# mcat-4cu-b-v2.net
KiCad netlist of a schematic drawn in EAGLE
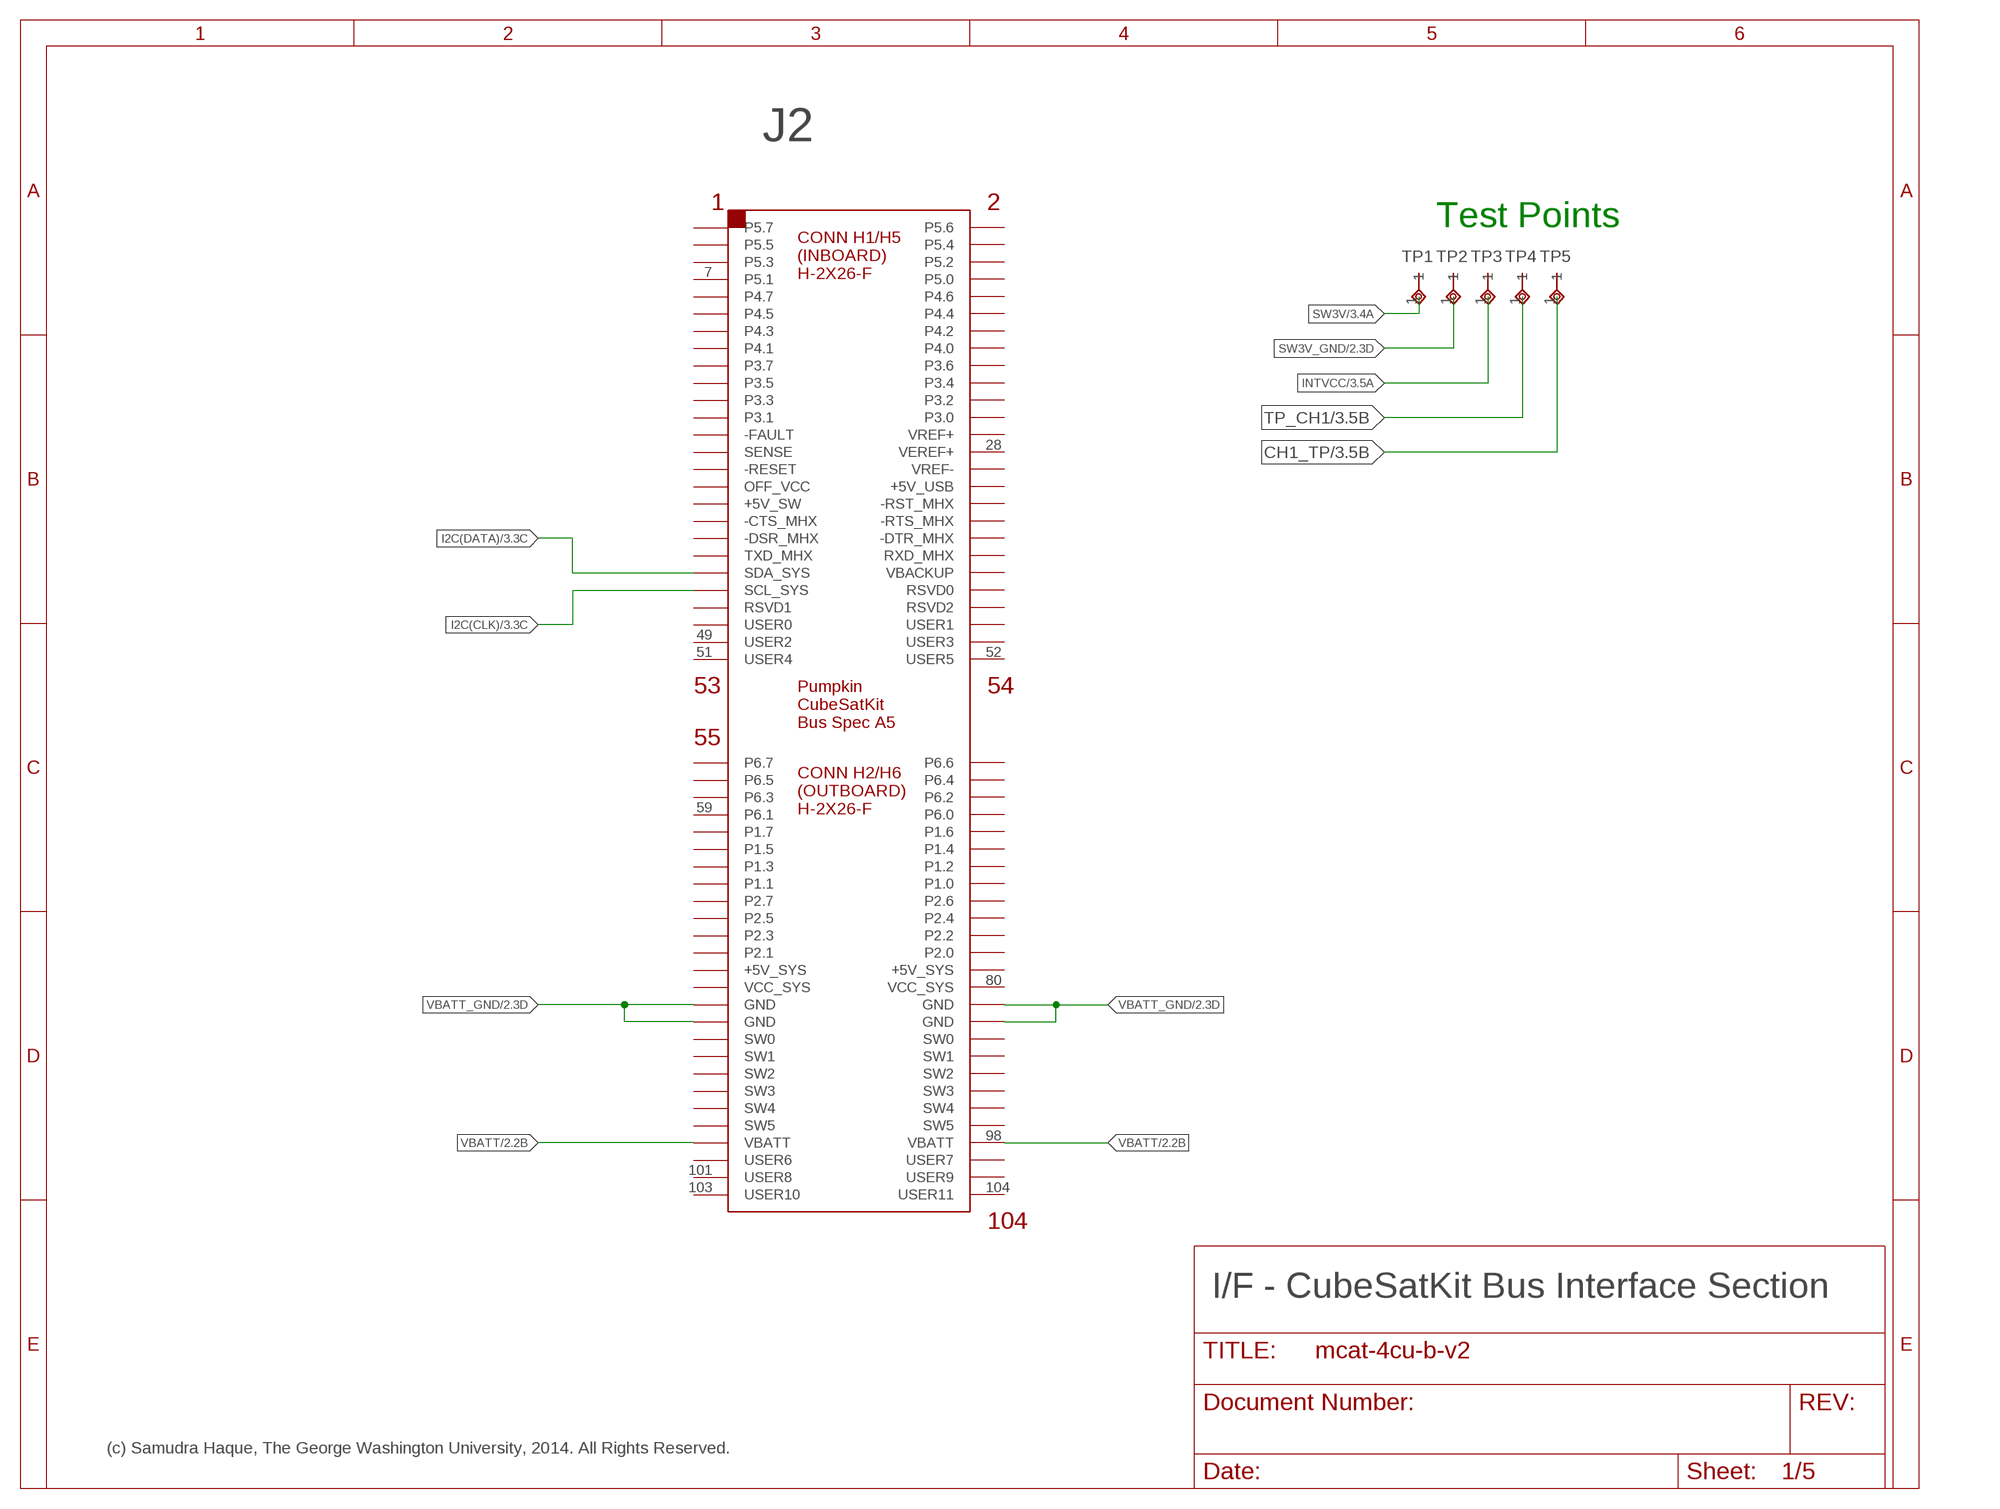
[diagram p0: schematic, sheet 1]
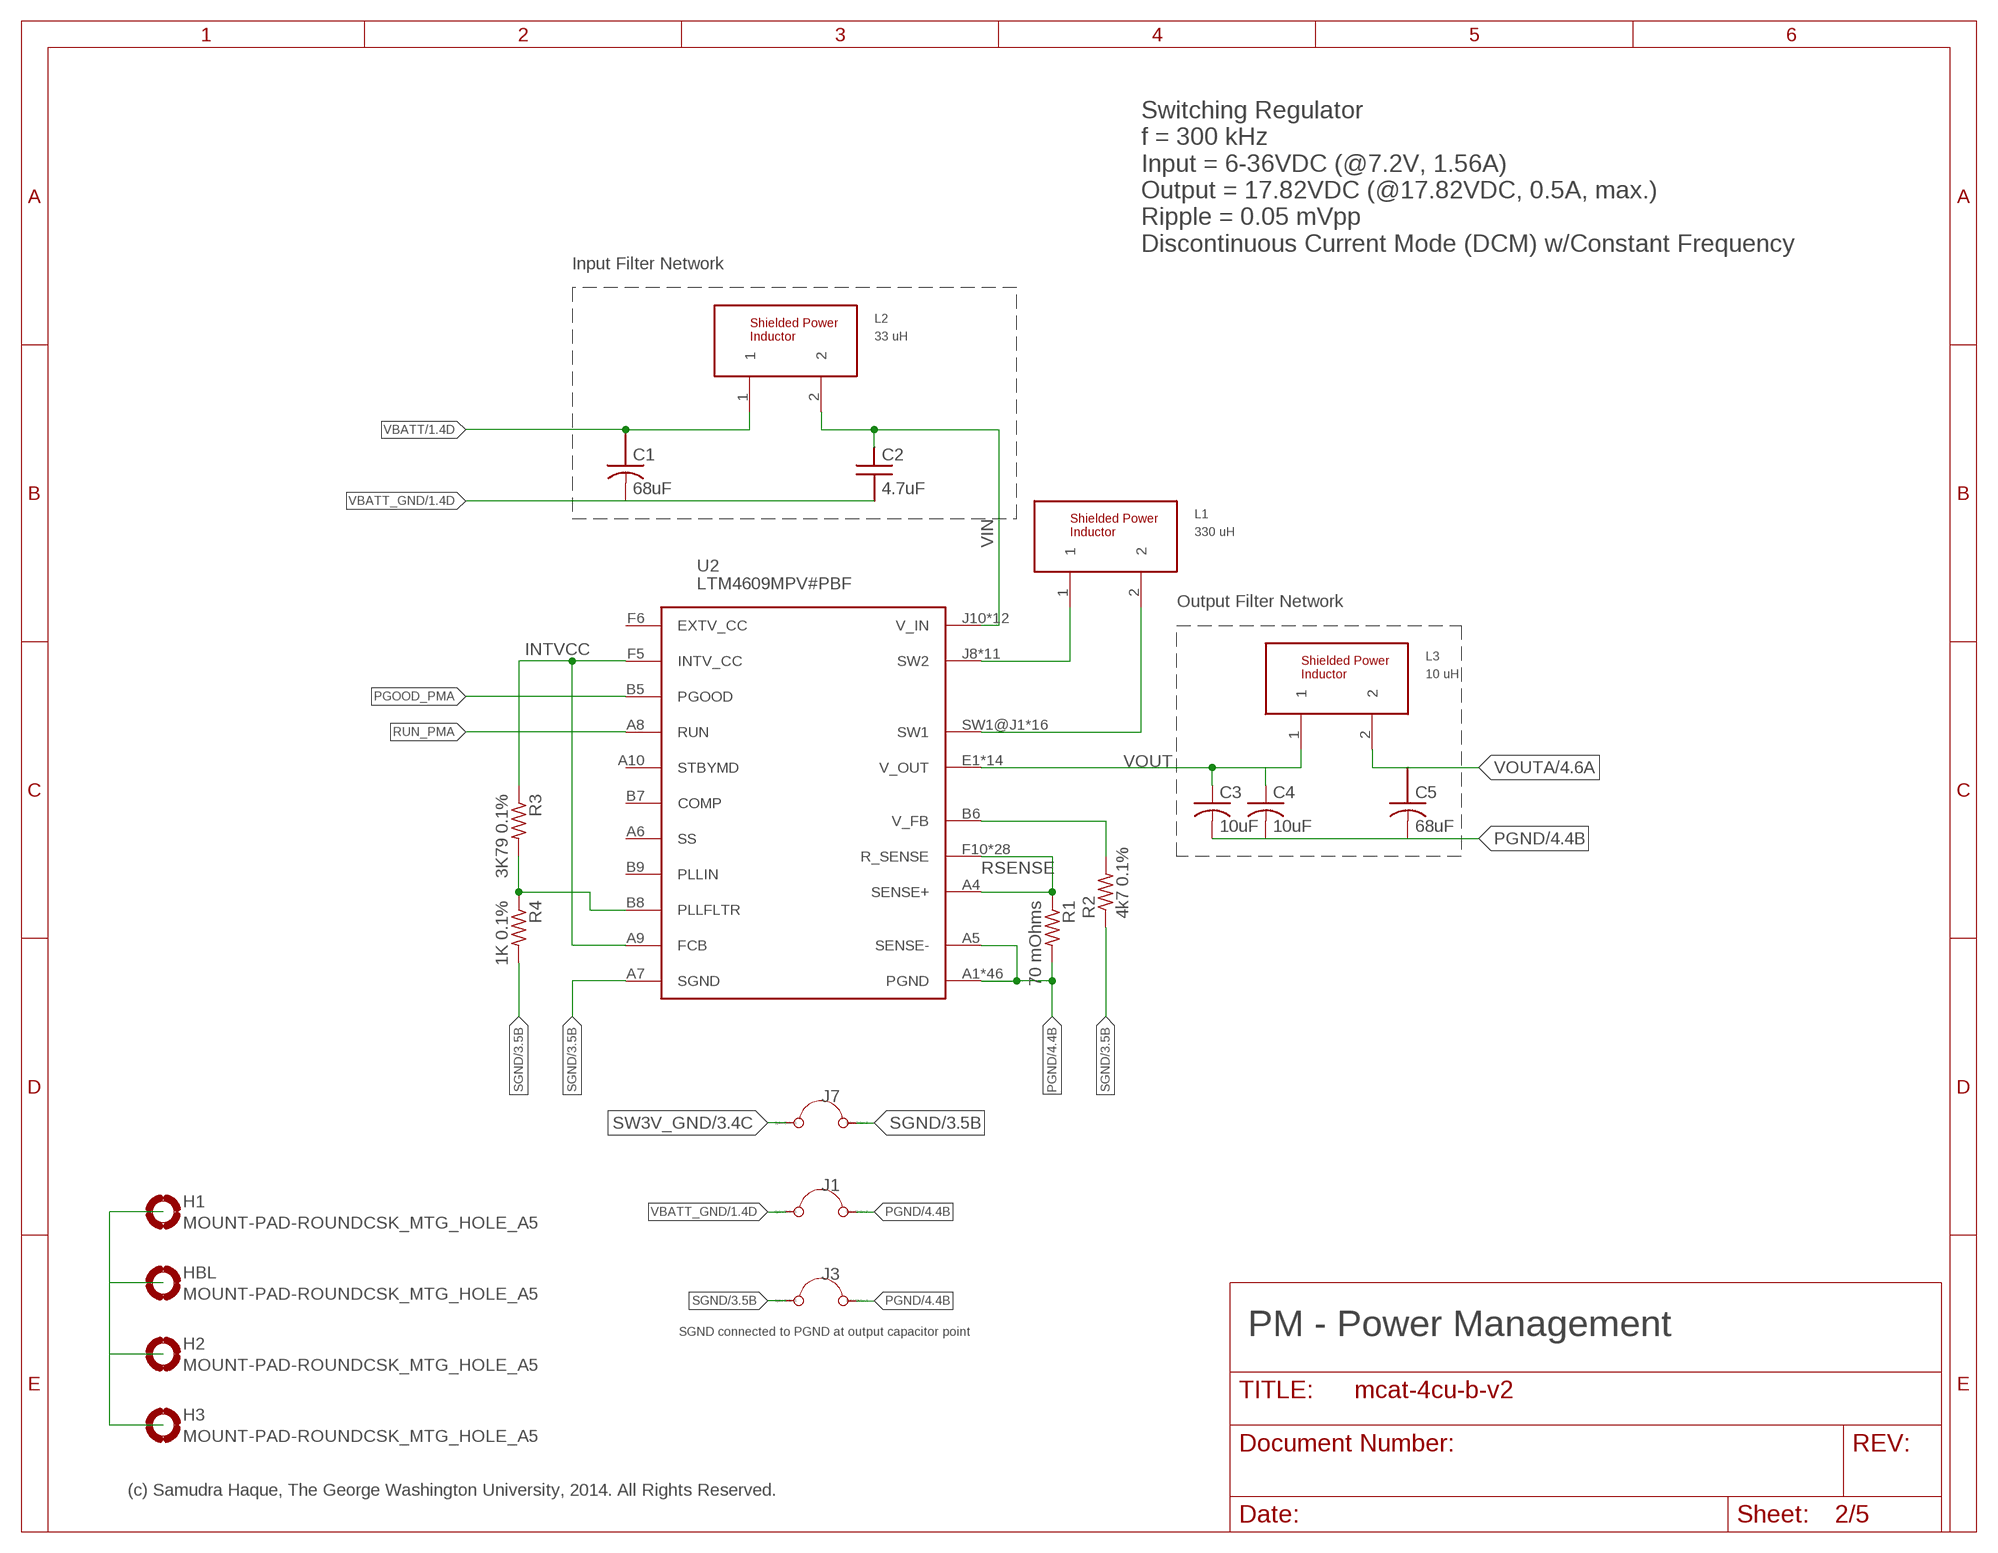
[diagram p1: schematic, sheet 2]
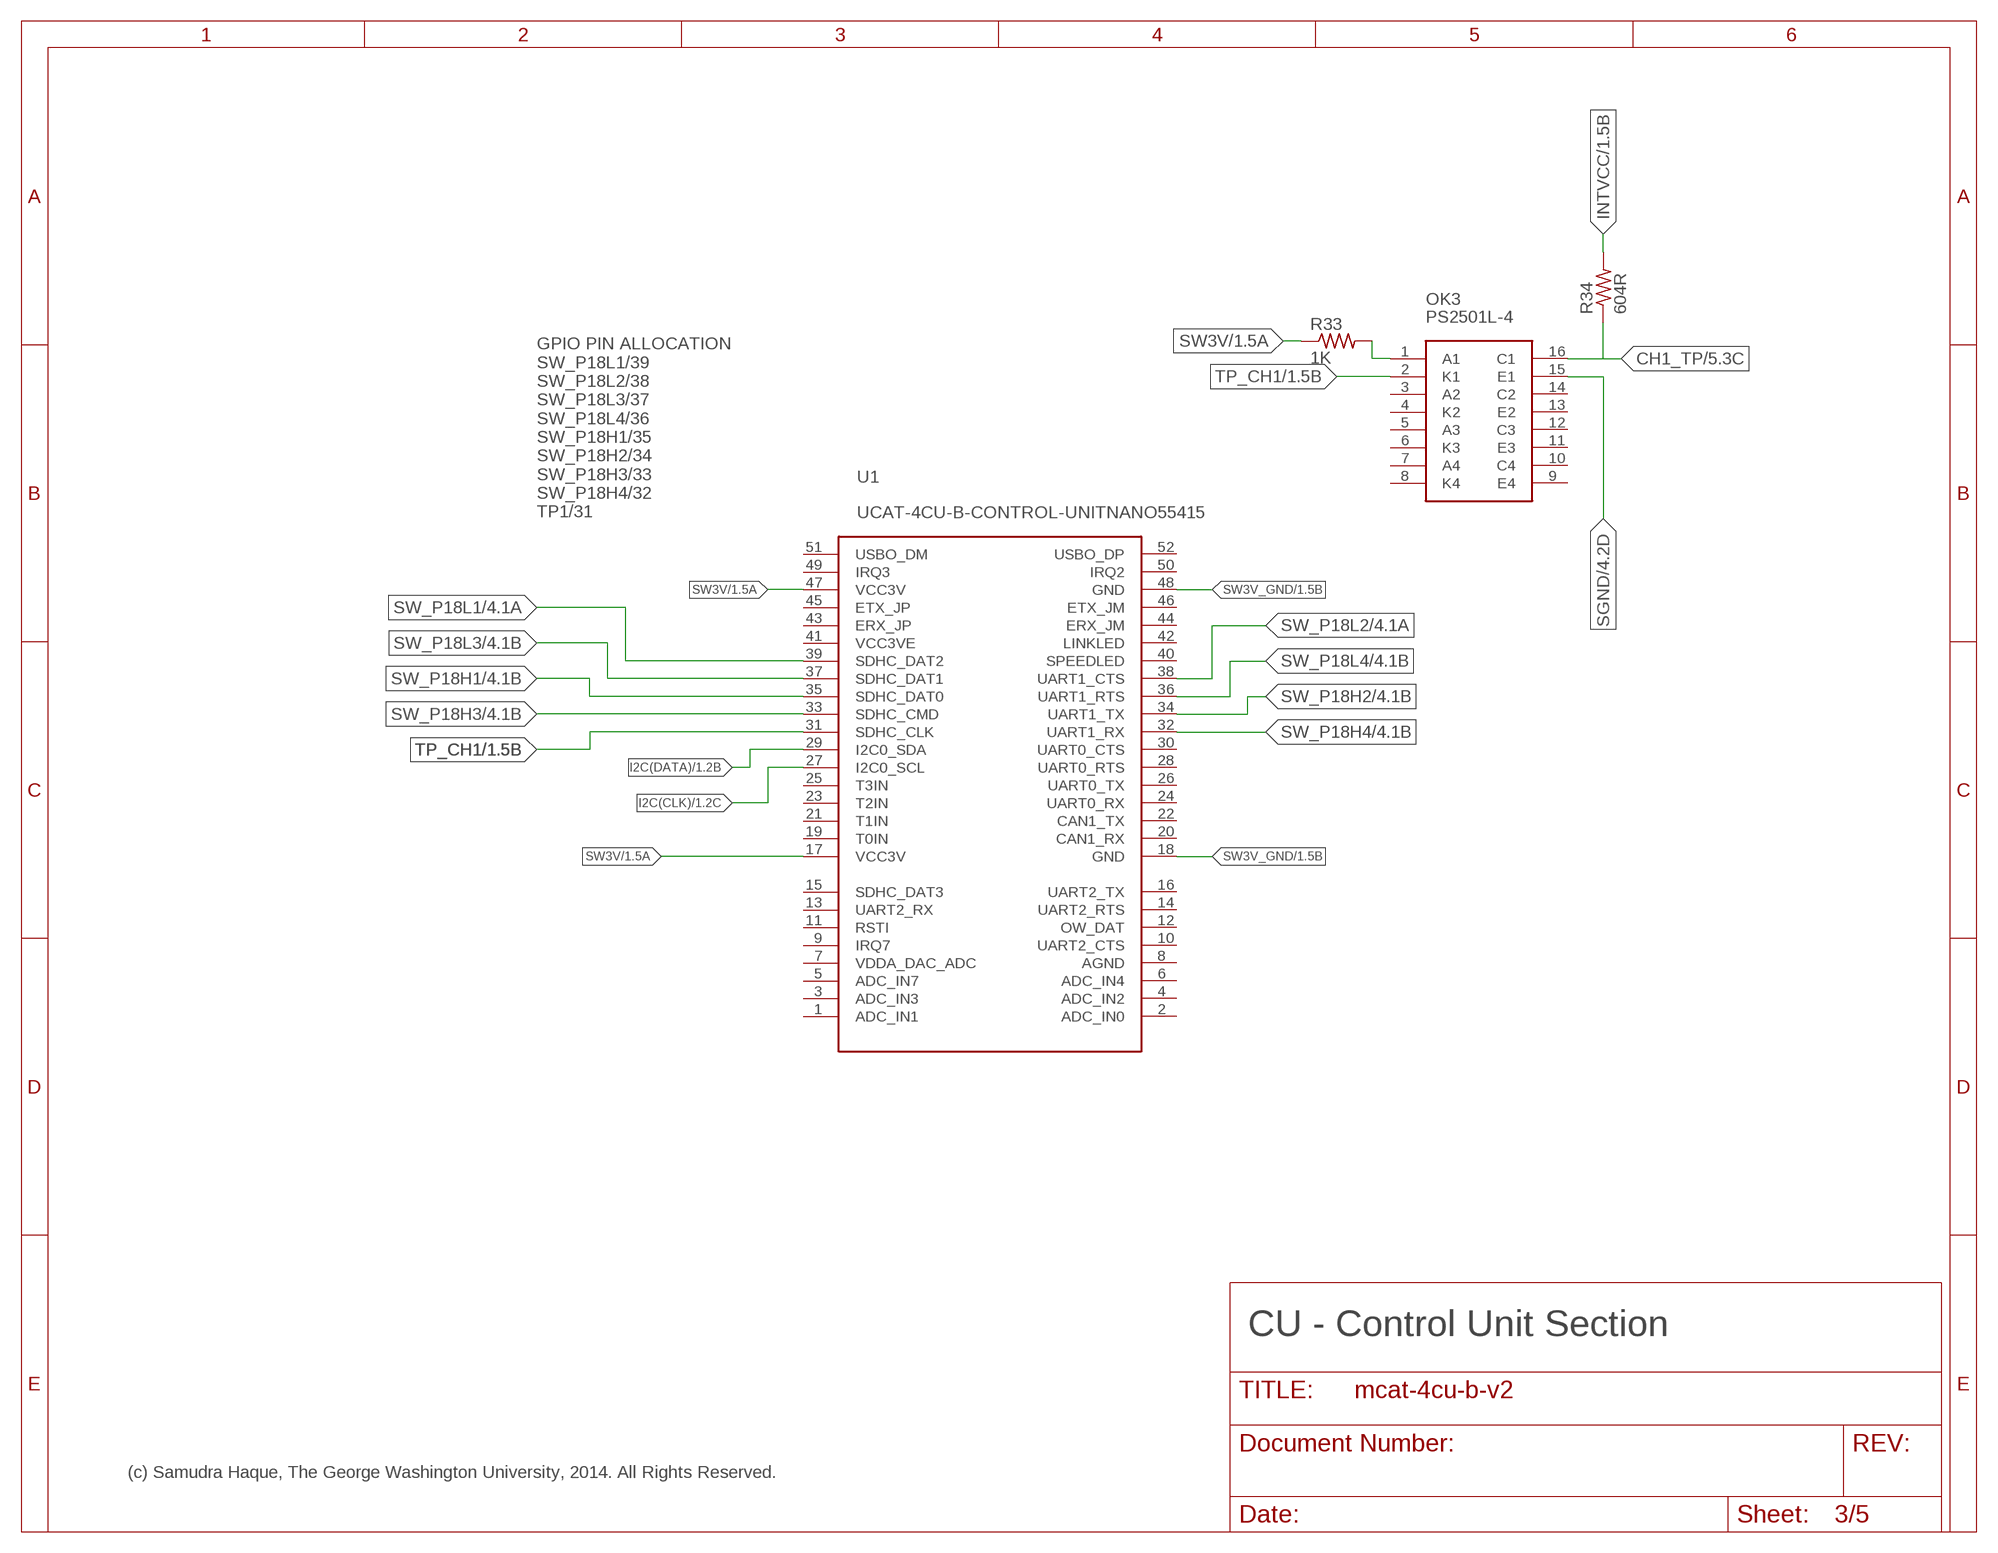
[diagram p2: schematic, sheet 3]
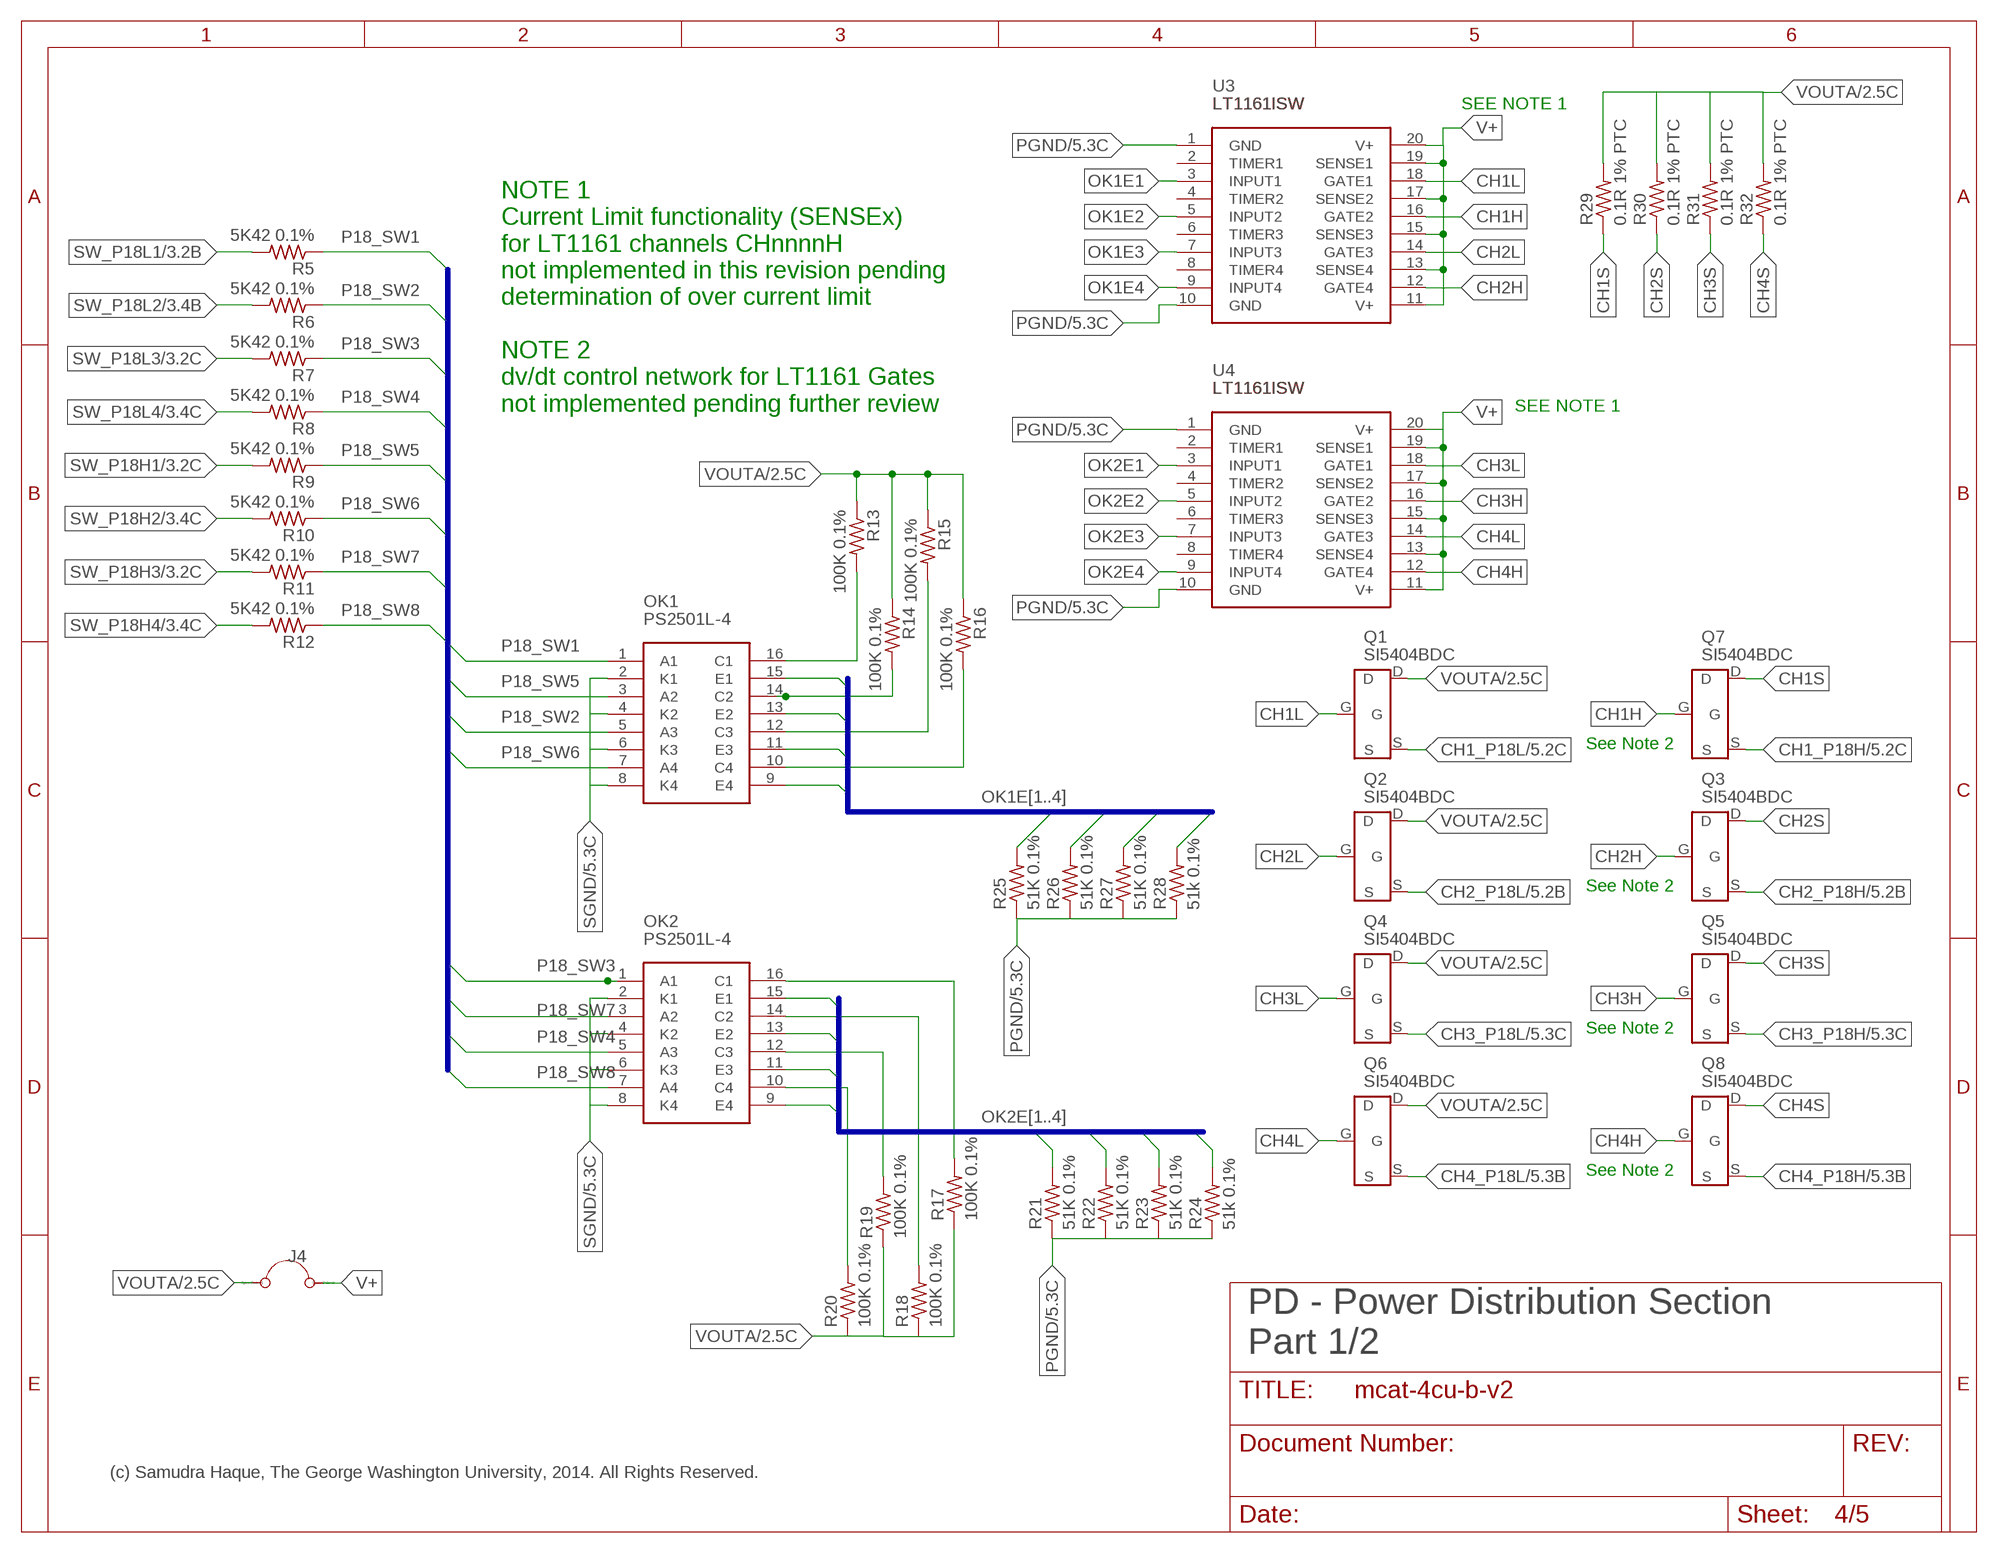
[diagram p3: schematic, sheet 4]
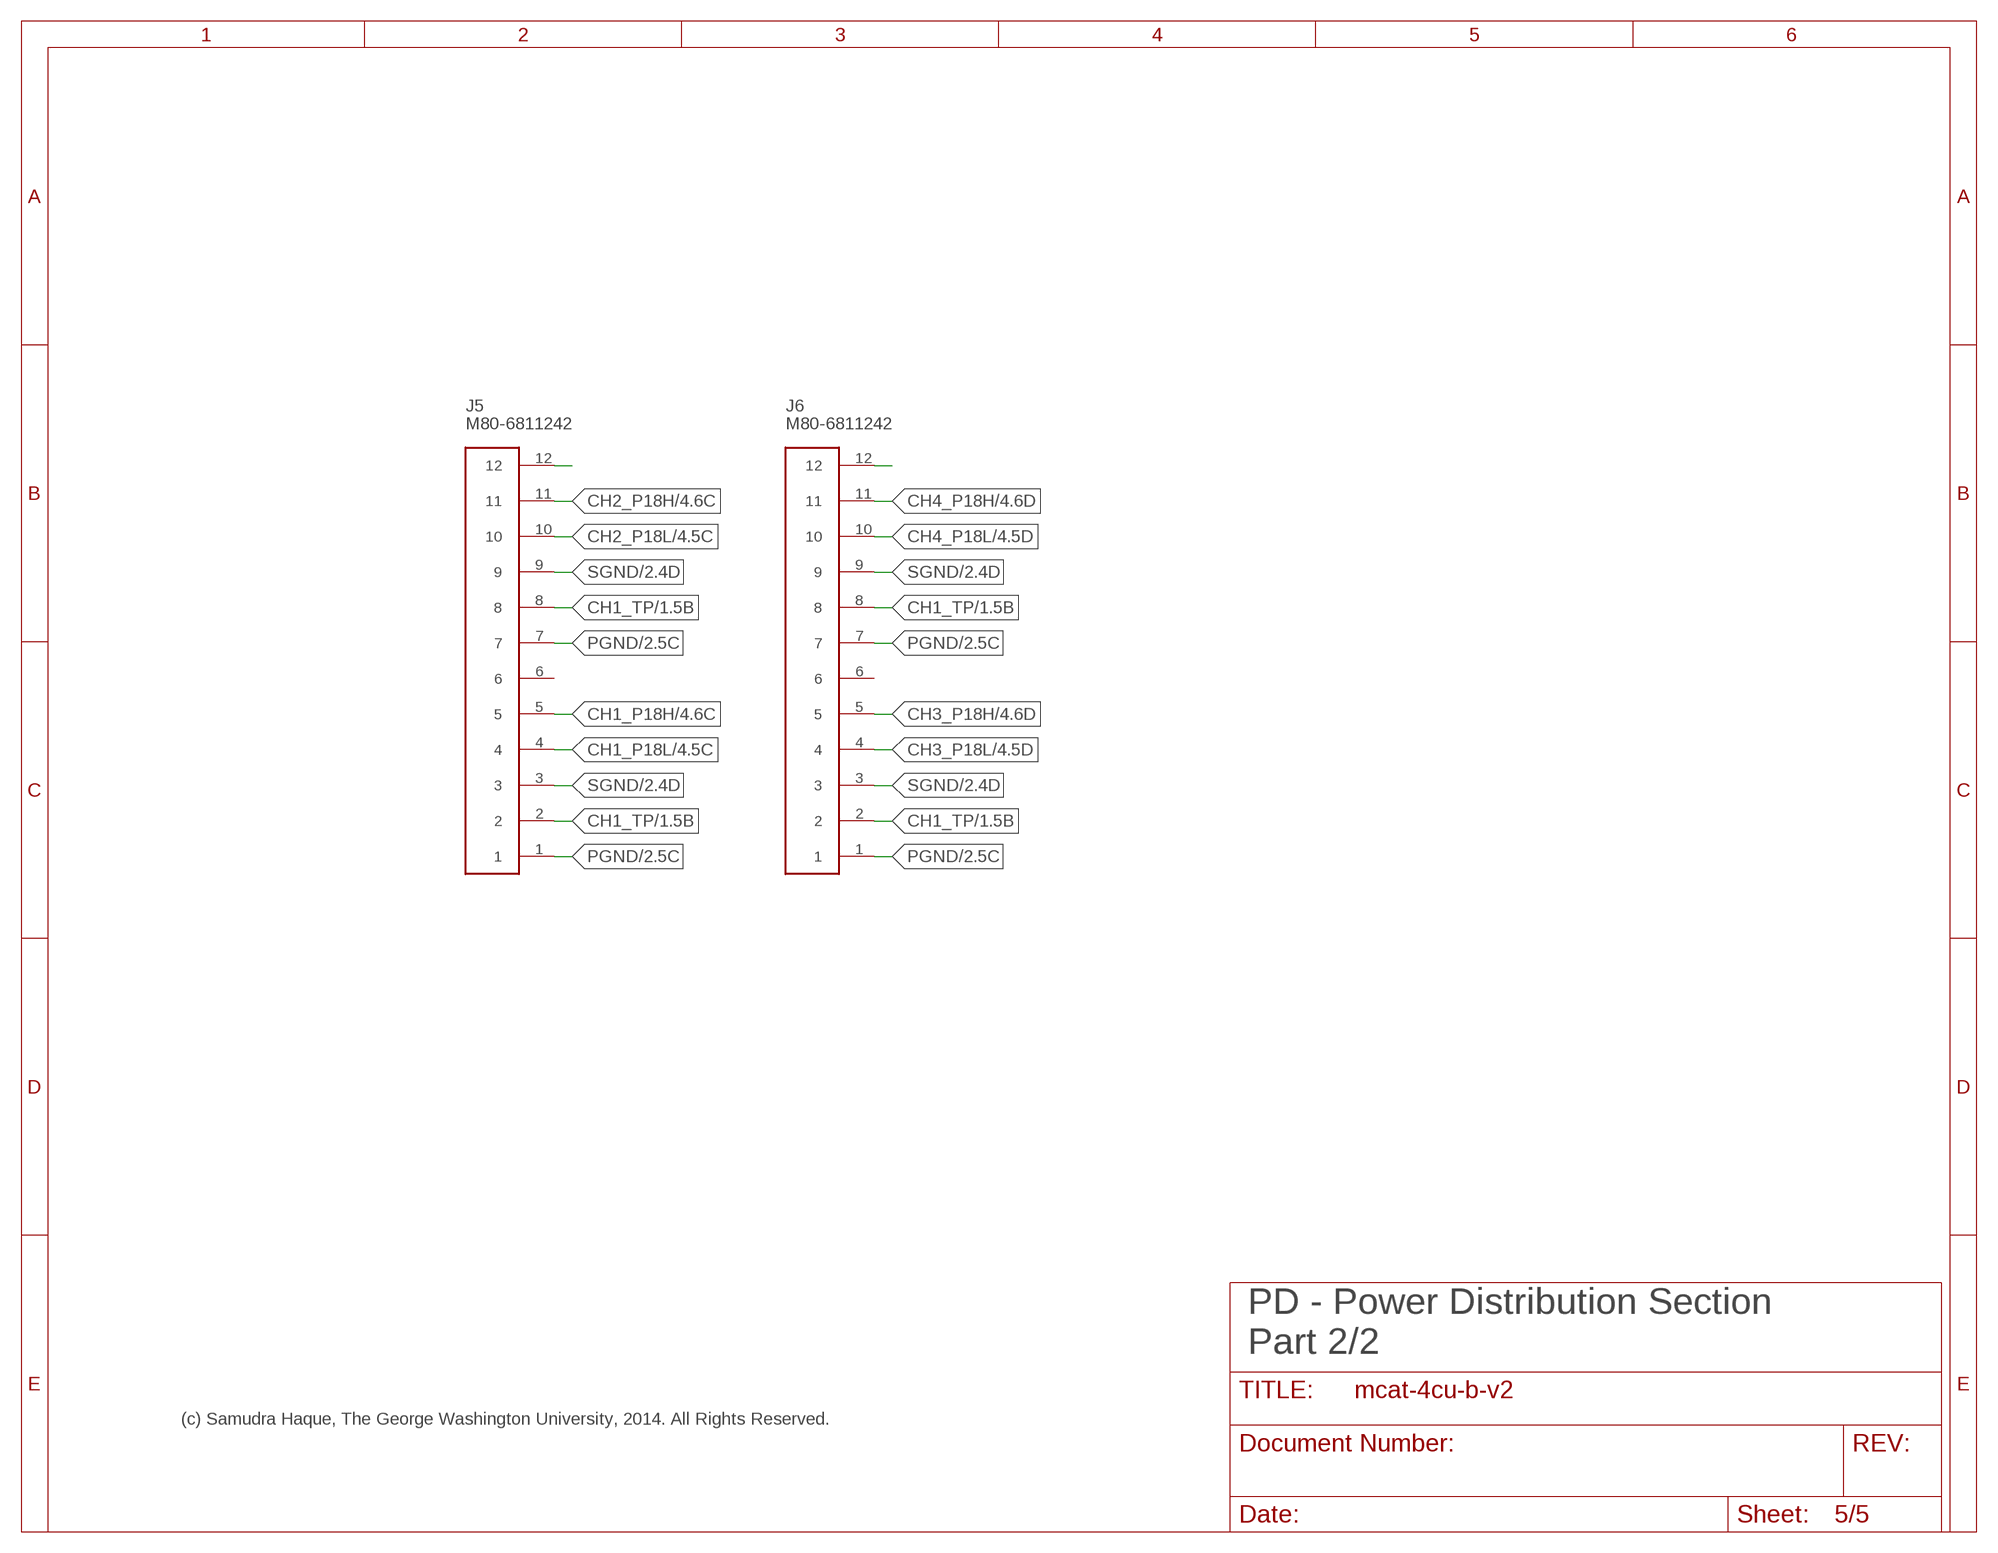
[diagram p4: schematic, sheet 5]

(export (version "E")
  (design (tool "Eeschema 10.0.6"))
  (components
    (comp (ref "J4")
      (value "JUMPER")
      (footprint "eagle-import:05")
      (libsource (lib "eagle-import") (part "JUMPER"))
    )
    (comp (ref "OK1")
      (value "PS2501L-4")
      (footprint "eagle-import:PS2501L-4")
      (libsource (lib "eagle-import") (part "PS2501L-4"))
    )
    (comp (ref "OK2")
      (value "PS2501L-4")
      (footprint "eagle-import:PS2501L-4")
      (libsource (lib "eagle-import") (part "PS2501L-4"))
    )
    (comp (ref "Q1")
      (value "SI5404BDC")
      (footprint "eagle-import:1206-8-CHIPFET")
      (libsource (lib "eagle-import") (part "SI5404BDC"))
    )
    (comp (ref "Q2")
      (value "SI5404BDC")
      (footprint "eagle-import:1206-8-CHIPFET")
      (libsource (lib "eagle-import") (part "SI5404BDC"))
    )
    (comp (ref "Q3")
      (value "SI5404BDC")
      (footprint "eagle-import:1206-8-CHIPFET")
      (libsource (lib "eagle-import") (part "SI5404BDC"))
    )
    (comp (ref "Q4")
      (value "SI5404BDC")
      (footprint "eagle-import:1206-8-CHIPFET")
      (libsource (lib "eagle-import") (part "SI5404BDC"))
    )
    (comp (ref "Q5")
      (value "SI5404BDC")
      (footprint "eagle-import:1206-8-CHIPFET")
      (libsource (lib "eagle-import") (part "SI5404BDC"))
    )
    (comp (ref "Q6")
      (value "SI5404BDC")
      (footprint "eagle-import:1206-8-CHIPFET")
      (libsource (lib "eagle-import") (part "SI5404BDC"))
    )
    (comp (ref "Q7")
      (value "SI5404BDC")
      (footprint "eagle-import:1206-8-CHIPFET")
      (libsource (lib "eagle-import") (part "SI5404BDC"))
    )
    (comp (ref "Q8")
      (value "SI5404BDC")
      (footprint "eagle-import:1206-8-CHIPFET")
      (libsource (lib "eagle-import") (part "SI5404BDC"))
    )
    (comp (ref "R5")
      (value "5K42 0.1%")
      (footprint "eagle-import:R1206")
      (libsource (lib "eagle-import") (part "resistor_R-US_R1206"))
    )
    (comp (ref "R6")
      (value "5K42 0.1%")
      (footprint "eagle-import:R1206")
      (libsource (lib "eagle-import") (part "resistor_R-US_R1206"))
    )
    (comp (ref "R7")
      (value "5K42 0.1%")
      (footprint "eagle-import:R1206")
      (libsource (lib "eagle-import") (part "resistor_R-US_R1206"))
    )
    (comp (ref "R8")
      (value "5K42 0.1%")
      (footprint "eagle-import:R1206")
      (libsource (lib "eagle-import") (part "resistor_R-US_R1206"))
    )
    (comp (ref "R9")
      (value "5K42 0.1%")
      (footprint "eagle-import:R1206")
      (libsource (lib "eagle-import") (part "resistor_R-US_R1206"))
    )
    (comp (ref "R10")
      (value "5K42 0.1%")
      (footprint "eagle-import:R1206")
      (libsource (lib "eagle-import") (part "resistor_R-US_R1206"))
    )
    (comp (ref "R11")
      (value "5K42 0.1%")
      (footprint "eagle-import:R1206")
      (libsource (lib "eagle-import") (part "resistor_R-US_R1206"))
    )
    (comp (ref "R12")
      (value "5K42 0.1%")
      (footprint "eagle-import:R1206")
      (libsource (lib "eagle-import") (part "resistor_R-US_R1206"))
    )
    (comp (ref "R13")
      (value "100K 0.1%")
      (footprint "eagle-import:R0402")
      (libsource (lib "eagle-import") (part "resistor_R-US_R0402"))
    )
    (comp (ref "R14")
      (value "100K 0.1%")
      (footprint "eagle-import:R0402")
      (libsource (lib "eagle-import") (part "resistor_R-US_R0402"))
    )
    (comp (ref "R15")
      (value "100K 0.1%")
      (footprint "eagle-import:R0402")
      (libsource (lib "eagle-import") (part "resistor_R-US_R0402"))
    )
    (comp (ref "R16")
      (value "100K 0.1%")
      (footprint "eagle-import:R0402")
      (libsource (lib "eagle-import") (part "resistor_R-US_R0402"))
    )
    (comp (ref "R17")
      (value "100K 0.1%")
      (footprint "eagle-import:R0402")
      (libsource (lib "eagle-import") (part "resistor_R-US_R0402"))
    )
    (comp (ref "R18")
      (value "100K 0.1%")
      (footprint "eagle-import:R0402")
      (libsource (lib "eagle-import") (part "resistor_R-US_R0402"))
    )
    (comp (ref "R19")
      (value "100K 0.1%")
      (footprint "eagle-import:R0402")
      (libsource (lib "eagle-import") (part "resistor_R-US_R0402"))
    )
    (comp (ref "R20")
      (value "100K 0.1%")
      (footprint "eagle-import:R0402")
      (libsource (lib "eagle-import") (part "resistor_R-US_R0402"))
    )
    (comp (ref "R21")
      (value "51K 0.1%")
      (footprint "eagle-import:R0603")
      (libsource (lib "eagle-import") (part "resistor_R-US_R0603"))
    )
    (comp (ref "R22")
      (value "51K 0.1%")
      (footprint "eagle-import:R0603")
      (libsource (lib "eagle-import") (part "resistor_R-US_R0603"))
    )
    (comp (ref "R23")
      (value "51K 0.1%")
      (footprint "eagle-import:R0603")
      (libsource (lib "eagle-import") (part "resistor_R-US_R0603"))
    )
    (comp (ref "R24")
      (value "51k 0.1%")
      (footprint "eagle-import:R0603")
      (libsource (lib "eagle-import") (part "resistor_R-US_R0603"))
    )
    (comp (ref "R25")
      (value "51K 0.1%")
      (footprint "eagle-import:R0603")
      (libsource (lib "eagle-import") (part "resistor_R-US_R0603"))
    )
    (comp (ref "R26")
      (value "51K 0.1%")
      (footprint "eagle-import:R0603")
      (libsource (lib "eagle-import") (part "resistor_R-US_R0603"))
    )
    (comp (ref "R27")
      (value "51K 0.1%")
      (footprint "eagle-import:R0603")
      (libsource (lib "eagle-import") (part "resistor_R-US_R0603"))
    )
    (comp (ref "R28")
      (value "51k 0.1%")
      (footprint "eagle-import:R0603")
      (libsource (lib "eagle-import") (part "resistor_R-US_R0603"))
    )
    (comp (ref "R29")
      (value "0.1R 1% PTC")
      (footprint "eagle-import:R0402")
      (libsource (lib "eagle-import") (part "R-US_R0402"))
    )
    (comp (ref "R30")
      (value "0.1R 1% PTC")
      (footprint "eagle-import:R0402")
      (libsource (lib "eagle-import") (part "R-US_R0402"))
    )
    (comp (ref "R31")
      (value "0.1R 1% PTC")
      (footprint "eagle-import:R0402")
      (libsource (lib "eagle-import") (part "R-US_R0402"))
    )
    (comp (ref "R32")
      (value "0.1R 1% PTC")
      (footprint "eagle-import:R0402")
      (libsource (lib "eagle-import") (part "R-US_R0402"))
    )
    (comp (ref "U3")
      (value "LT1161ISW")
      (footprint "eagle-import:20-LEAD-PLASTIC-SO")
      (libsource (lib "eagle-import") (part "LT1161ISW"))
    )
    (comp (ref "U4")
      (value "LT1161ISW")
      (footprint "eagle-import:20-LEAD-PLASTIC-SO")
      (libsource (lib "eagle-import") (part "LT1161ISW"))
    )
    (comp (ref "J5")
      (value "M80-6811242")
      (footprint "eagle-import:M80-68112")
      (libsource (lib "eagle-import") (part "M80-6811242"))
    )
    (comp (ref "J6")
      (value "M80-6811242")
      (footprint "eagle-import:M80-68112")
      (libsource (lib "eagle-import") (part "M80-6811242"))
    )
    (comp (ref "OK3")
      (value "PS2501L-4")
      (footprint "eagle-import:PS2501L-4")
      (libsource (lib "eagle-import") (part "PS2501L-4"))
    )
    (comp (ref "R33")
      (value "1K")
      (footprint "eagle-import:R0805")
      (libsource (lib "eagle-import") (part "resistor_R-US_R0805"))
    )
    (comp (ref "R34")
      (value "604R")
      (footprint "eagle-import:R0805")
      (libsource (lib "eagle-import") (part "resistor_R-US_R0805"))
    )
    (comp (ref "U1")
      (value "UCAT-4CU-B-CONTROL-UNITNANO55415")
      (footprint "eagle-import:MOLEX-MINI-PCI-EXPRESS-8MM-52CKT")
      (libsource (lib "eagle-import") (part "UCAT-4CU-B-CONTROL-UNITNANO55415"))
    )
    (comp (ref "J2")
      (value "CSK-BUS-CONN2X2X26")
      (footprint "eagle-import:CSK-BUS-PKG")
      (libsource (lib "eagle-import") (part "CSK-BUS-CONN2X2X26"))
    )
    (comp (ref "TP1")
      (value "1P-1508-0-57-15-00-00-03-0")
      (footprint "eagle-import:1P-TP-MILLMAX-11")
      (libsource (lib "eagle-import") (part "1P-1508-0-57-15-00-00-03-0"))
    )
    (comp (ref "TP2")
      (value "1P-1508-0-57-15-00-00-03-0")
      (footprint "eagle-import:1P-TP-MILLMAX-11")
      (libsource (lib "eagle-import") (part "1P-1508-0-57-15-00-00-03-0"))
    )
    (comp (ref "TP3")
      (value "1P-1508-0-57-15-00-00-03-0")
      (footprint "eagle-import:1P-TP-MILLMAX-11")
      (libsource (lib "eagle-import") (part "1P-1508-0-57-15-00-00-03-0"))
    )
    (comp (ref "TP4")
      (value "1P-1508-0-57-15-00-00-03-0")
      (footprint "eagle-import:1P-TP-MILLMAX-11")
      (libsource (lib "eagle-import") (part "1P-1508-0-57-15-00-00-03-0"))
    )
    (comp (ref "TP5")
      (value "1P-1508-0-57-15-00-00-03-0")
      (footprint "eagle-import:1P-TP-MILLMAX-11")
      (libsource (lib "eagle-import") (part "1P-1508-0-57-15-00-00-03-0"))
    )
    (comp (ref "C1")
      (value "68uF")
      (footprint "eagle-import:OS-CON-SVPF-F12")
      (libsource (lib "eagle-import") (part "OSCON-50SVPF68M"))
    )
    (comp (ref "C2")
      (value "4.7uF")
      (footprint "eagle-import:MLCC-X7R-1210")
      (libsource (lib "eagle-import") (part "AVX-LD105C475KAB2A"))
    )
    (comp (ref "C3")
      (value "10uF")
      (footprint "eagle-import:C1210K")
      (libsource (lib "eagle-import") (part "C-USC1210K"))
    )
    (comp (ref "C4")
      (value "10uF")
      (footprint "eagle-import:C1210K")
      (libsource (lib "eagle-import") (part "C-USC1210K"))
    )
    (comp (ref "C5")
      (value "68uF")
      (footprint "eagle-import:OS-CON-SVPF-F12")
      (libsource (lib "eagle-import") (part "OSCON-50SVPF68M"))
    )
    (comp (ref "H1")
      (value "MOUNT-PAD-ROUNDCSK_MTG_HOLE_A5")
      (footprint "eagle-import:CSK_MOUNTING_HOLE")
      (libsource (lib "eagle-import") (part "MOUNT-PAD-ROUNDCSK_MTG_HOLE_A5"))
    )
    (comp (ref "H2")
      (value "MOUNT-PAD-ROUNDCSK_MTG_HOLE_A5")
      (footprint "eagle-import:CSK_MOUNTING_HOLE")
      (libsource (lib "eagle-import") (part "MOUNT-PAD-ROUNDCSK_MTG_HOLE_A5"))
    )
    (comp (ref "H3")
      (value "MOUNT-PAD-ROUNDCSK_MTG_HOLE_A5")
      (footprint "eagle-import:CSK_MOUNTING_HOLE")
      (libsource (lib "eagle-import") (part "MOUNT-PAD-ROUNDCSK_MTG_HOLE_A5"))
    )
    (comp (ref "HBL")
      (value "MOUNT-PAD-ROUNDCSK_MTG_HOLE_A5")
      (footprint "eagle-import:CSK_MOUNTING_HOLE")
      (libsource (lib "eagle-import") (part "MOUNT-PAD-ROUNDCSK_MTG_HOLE_A5"))
    )
    (comp (ref "J1")
      (value "JUMPER")
      (footprint "eagle-import:05")
      (libsource (lib "eagle-import") (part "JUMPER"))
    )
    (comp (ref "J3")
      (value "JUMPER")
      (footprint "eagle-import:05")
      (libsource (lib "eagle-import") (part "JUMPER"))
    )
    (comp (ref "J7")
      (value "JUMPER")
      (footprint "eagle-import:05")
      (libsource (lib "eagle-import") (part "JUMPER"))
    )
    (comp (ref "L1")
      (value "330 uH")
      (footprint "eagle-import:MSS1048")
      (libsource (lib "eagle-import") (part "MSS1048-334KL_"))
    )
    (comp (ref "L2")
      (value "33 uH")
      (footprint "eagle-import:MSS1048")
      (libsource (lib "eagle-import") (part "MSS1038-333ML_"))
    )
    (comp (ref "L3")
      (value "10 uH")
      (footprint "eagle-import:SERIES-POWER-INDUCTORS")
      (fields (field (name "MF") "PANASONIC") (field (name "MPN") "ELL5PS100M"))
      (libsource (lib "eagle-import") (part "ELL-5PS100M"))
    )
    (comp (ref "R1")
      (value "70 mOhms")
      (footprint "eagle-import:R1206")
      (libsource (lib "eagle-import") (part "resistor_R-US_R1206"))
    )
    (comp (ref "R2")
      (value "4k7 0.1%")
      (footprint "eagle-import:R0603")
      (libsource (lib "eagle-import") (part "resistor_R-US_R0603"))
    )
    (comp (ref "R3")
      (value "3K79 0.1%")
      (footprint "eagle-import:R0805")
      (libsource (lib "eagle-import") (part "R-US_R0805"))
    )
    (comp (ref "R4")
      (value "1K 0.1%")
      (footprint "eagle-import:R0805")
      (libsource (lib "eagle-import") (part "R-US_R0805"))
    )
    (comp (ref "U2")
      (value "LTM4609MPV#PBF")
      (footprint "eagle-import:LGA-141-LTC-05-08-1840-B")
      (libsource (lib "eagle-import") (part "LTM4609MPV#PBFROHS/HITEMP"))
    )
  )
  (nets
    (net (code "3") (name "CH1H") (class "Default")
      (node (ref "Q7") (pin "G") (pinfunction "G_G") (pintype "bidirectional"))
      (node (ref "U3") (pin "16") (pinfunction "GATE2_16") (pintype "bidirectional"))
    )
    (net (code "4") (name "CH1L") (class "Default")
      (node (ref "Q1") (pin "G") (pinfunction "G_G") (pintype "bidirectional"))
      (node (ref "U3") (pin "18") (pinfunction "GATE1_18") (pintype "bidirectional"))
    )
    (net (code "5") (name "CH1S") (class "Default")
      (node (ref "Q7") (pin "D") (pinfunction "D_D") (pintype "bidirectional"))
      (node (ref "R29") (pin "1") (pinfunction "1_1") (pintype "passive"))
    )
    (net (code "6") (name "CH1_P18H") (class "Default")
      (node (ref "J5") (pin "5") (pinfunction "5_5") (pintype "bidirectional"))
      (node (ref "Q7") (pin "S") (pinfunction "S_S") (pintype "bidirectional"))
    )
    (net (code "7") (name "CH1_P18L") (class "Default")
      (node (ref "J5") (pin "4") (pinfunction "4_4") (pintype "bidirectional"))
      (node (ref "Q1") (pin "S") (pinfunction "S_S") (pintype "bidirectional"))
    )
    (net (code "8") (name "CH1_TP") (class "Default")
      (node (ref "J5") (pin "2") (pinfunction "2_2") (pintype "bidirectional"))
      (node (ref "J5") (pin "8") (pinfunction "8_8") (pintype "bidirectional"))
      (node (ref "J6") (pin "2") (pinfunction "2_2") (pintype "bidirectional"))
      (node (ref "J6") (pin "8") (pinfunction "8_8") (pintype "bidirectional"))
      (node (ref "OK3") (pin "16") (pinfunction "C1_16") (pintype "bidirectional"))
      (node (ref "R34") (pin "1") (pinfunction "1_1") (pintype "passive"))
      (node (ref "TP5") (pin "1") (pinfunction "1_1") (pintype "bidirectional"))
    )
    (net (code "9") (name "CH2H") (class "Default")
      (node (ref "Q3") (pin "G") (pinfunction "G_G") (pintype "bidirectional"))
      (node (ref "U3") (pin "12") (pinfunction "GATE4_12") (pintype "bidirectional"))
    )
    (net (code "10") (name "CH2L") (class "Default")
      (node (ref "Q2") (pin "G") (pinfunction "G_G") (pintype "bidirectional"))
      (node (ref "U3") (pin "14") (pinfunction "GATE3_14") (pintype "bidirectional"))
    )
    (net (code "11") (name "CH2S") (class "Default")
      (node (ref "Q3") (pin "D") (pinfunction "D_D") (pintype "bidirectional"))
      (node (ref "R30") (pin "1") (pinfunction "1_1") (pintype "passive"))
    )
    (net (code "12") (name "CH2_P18H") (class "Default")
      (node (ref "J5") (pin "11") (pinfunction "11_11") (pintype "bidirectional"))
      (node (ref "Q3") (pin "S") (pinfunction "S_S") (pintype "bidirectional"))
    )
    (net (code "13") (name "CH2_P18L") (class "Default")
      (node (ref "J5") (pin "10") (pinfunction "10_10") (pintype "bidirectional"))
      (node (ref "Q2") (pin "S") (pinfunction "S_S") (pintype "bidirectional"))
    )
    (net (code "14") (name "CH3H") (class "Default")
      (node (ref "Q5") (pin "G") (pinfunction "G_G") (pintype "bidirectional"))
      (node (ref "U4") (pin "16") (pinfunction "GATE2_16") (pintype "bidirectional"))
    )
    (net (code "15") (name "CH3L") (class "Default")
      (node (ref "Q4") (pin "G") (pinfunction "G_G") (pintype "bidirectional"))
      (node (ref "U4") (pin "18") (pinfunction "GATE1_18") (pintype "bidirectional"))
    )
    (net (code "16") (name "CH3S") (class "Default")
      (node (ref "Q5") (pin "D") (pinfunction "D_D") (pintype "bidirectional"))
      (node (ref "R31") (pin "1") (pinfunction "1_1") (pintype "passive"))
    )
    (net (code "17") (name "CH3_P18H") (class "Default")
      (node (ref "J6") (pin "5") (pinfunction "5_5") (pintype "bidirectional"))
      (node (ref "Q5") (pin "S") (pinfunction "S_S") (pintype "bidirectional"))
    )
    (net (code "18") (name "CH3_P18L") (class "Default")
      (node (ref "J6") (pin "4") (pinfunction "4_4") (pintype "bidirectional"))
      (node (ref "Q4") (pin "S") (pinfunction "S_S") (pintype "bidirectional"))
    )
    (net (code "19") (name "CH4H") (class "Default")
      (node (ref "Q8") (pin "G") (pinfunction "G_G") (pintype "bidirectional"))
      (node (ref "U4") (pin "12") (pinfunction "GATE4_12") (pintype "bidirectional"))
    )
    (net (code "20") (name "CH4L") (class "Default")
      (node (ref "Q6") (pin "G") (pinfunction "G_G") (pintype "bidirectional"))
      (node (ref "U4") (pin "14") (pinfunction "GATE3_14") (pintype "bidirectional"))
    )
    (net (code "21") (name "CH4S") (class "Default")
      (node (ref "Q8") (pin "D") (pinfunction "D_D") (pintype "bidirectional"))
      (node (ref "R32") (pin "1") (pinfunction "1_1") (pintype "passive"))
    )
    (net (code "22") (name "CH4_P18H") (class "Default")
      (node (ref "J6") (pin "11") (pinfunction "11_11") (pintype "bidirectional"))
      (node (ref "Q8") (pin "S") (pinfunction "S_S") (pintype "bidirectional"))
    )
    (net (code "23") (name "CH4_P18L") (class "Default")
      (node (ref "J6") (pin "10") (pinfunction "10_10") (pintype "bidirectional"))
      (node (ref "Q6") (pin "S") (pinfunction "S_S") (pintype "bidirectional"))
    )
    (net (code "24") (name "I2C(CLK)") (class "Default")
      (node (ref "J2") (pin "43") (pinfunction "SCL_SYS_43") (pintype "bidirectional"))
      (node (ref "U1") (pin "27") (pinfunction "I2C0_SCL_27") (pintype "bidirectional"))
    )
    (net (code "25") (name "I2C(DATA)") (class "Default")
      (node (ref "J2") (pin "41") (pinfunction "SDA_SYS_41") (pintype "bidirectional"))
      (node (ref "U1") (pin "29") (pinfunction "I2C0_SDA_29") (pintype "bidirectional"))
    )
    (net (code "26") (name "INTVCC") (class "Default")
      (node (ref "R3") (pin "1") (pinfunction "1_1") (pintype "passive"))
      (node (ref "R34") (pin "2") (pinfunction "2_2") (pintype "passive"))
      (node (ref "TP3") (pin "1") (pinfunction "1_1") (pintype "bidirectional"))
      (node (ref "U2") (pin "A9") (pinfunction "FCB_A9") (pintype "bidirectional"))
      (node (ref "U2") (pin "F5") (pinfunction "INTV_CC_F5") (pintype "bidirectional"))
    )
    (net (code "27") (name "Net-(H1-MOUNT)") (class "Default")
      (node (ref "H1") (pin "P$1") (pinfunction "MOUNT_P$1") (pintype "passive"))
      (node (ref "H2") (pin "P$1") (pinfunction "MOUNT_P$1") (pintype "passive"))
      (node (ref "H3") (pin "P$1") (pinfunction "MOUNT_P$1") (pintype "passive"))
      (node (ref "HBL") (pin "P$1") (pinfunction "MOUNT_P$1") (pintype "passive"))
    )
    (net (code "28") (name "Net-(L1-Pad1)") (class "Default")
      (node (ref "L1") (pin "1") (pinfunction "1_1") (pintype "bidirectional"))
      (node (ref "U2") (pin "J8") (pinfunction "SW2_J8") (pintype "bidirectional"))
      (node (ref "U2") (pin "J9") (pinfunction "SW2_J9") (pintype "bidirectional"))
      (node (ref "U2") (pin "K7") (pinfunction "SW2_K7") (pintype "bidirectional"))
      (node (ref "U2") (pin "K8") (pinfunction "SW2_K8") (pintype "bidirectional"))
      (node (ref "U2") (pin "K9") (pinfunction "SW2_K9") (pintype "bidirectional"))
      (node (ref "U2") (pin "L7") (pinfunction "SW2_L7") (pintype "bidirectional"))
      (node (ref "U2") (pin "L8") (pinfunction "SW2_L8") (pintype "bidirectional"))
      (node (ref "U2") (pin "L9") (pinfunction "SW2_L9") (pintype "bidirectional"))
      (node (ref "U2") (pin "M7") (pinfunction "SW2_M7") (pintype "bidirectional"))
      (node (ref "U2") (pin "M8") (pinfunction "SW2_M8") (pintype "bidirectional"))
      (node (ref "U2") (pin "M9") (pinfunction "SW2_M9") (pintype "bidirectional"))
    )
    (net (code "29") (name "Net-(L1-Pad2)") (class "Default")
      (node (ref "L1") (pin "2") (pinfunction "2_2") (pintype "bidirectional"))
      (node (ref "U2") (pin "SW1@J1") (pinfunction "SW1_SW1@J1") (pintype "bidirectional"))
      (node (ref "U2") (pin "SW1@J2") (pinfunction "SW1_SW1@J2") (pintype "bidirectional"))
      (node (ref "U2") (pin "SW1@J3") (pinfunction "SW1_SW1@J3") (pintype "bidirectional"))
      (node (ref "U2") (pin "SW1@J4") (pinfunction "SW1_SW1@J4") (pintype "bidirectional"))
      (node (ref "U2") (pin "SW1@K1") (pinfunction "SW1_SW1@K1") (pintype "bidirectional"))
      (node (ref "U2") (pin "SW1@K2") (pinfunction "SW1_SW1@K2") (pintype "bidirectional"))
      (node (ref "U2") (pin "SW1@K3") (pinfunction "SW1_SW1@K3") (pintype "bidirectional"))
      (node (ref "U2") (pin "SW1@K4") (pinfunction "SW1_SW1@K4") (pintype "bidirectional"))
      (node (ref "U2") (pin "SW1@L1") (pinfunction "SW1_SW1@L1") (pintype "bidirectional"))
      (node (ref "U2") (pin "SW1@L2") (pinfunction "SW1_SW1@L2") (pintype "bidirectional"))
      (node (ref "U2") (pin "SW1@L3") (pinfunction "SW1_SW1@L3") (pintype "bidirectional"))
      (node (ref "U2") (pin "SW1@L4") (pinfunction "SW1_SW1@L4") (pintype "bidirectional"))
      (node (ref "U2") (pin "SW1@M1") (pinfunction "SW1_SW1@M1") (pintype "bidirectional"))
      (node (ref "U2") (pin "SW1@M2") (pinfunction "SW1_SW1@M2") (pintype "bidirectional"))
      (node (ref "U2") (pin "SW1@M3") (pinfunction "SW1_SW1@M3") (pintype "bidirectional"))
      (node (ref "U2") (pin "SW1@M4") (pinfunction "SW1_SW1@M4") (pintype "bidirectional"))
    )
    (net (code "30") (name "Net-(OK1-C1)") (class "Default")
      (node (ref "OK1") (pin "16") (pinfunction "C1_16") (pintype "bidirectional"))
      (node (ref "R13") (pin "2") (pinfunction "2_2") (pintype "passive"))
    )
    (net (code "31") (name "Net-(OK1-C2)") (class "Default")
      (node (ref "OK1") (pin "14") (pinfunction "C2_14") (pintype "bidirectional"))
      (node (ref "R14") (pin "2") (pinfunction "2_2") (pintype "passive"))
    )
    (net (code "32") (name "Net-(OK1-C3)") (class "Default")
      (node (ref "OK1") (pin "12") (pinfunction "C3_12") (pintype "bidirectional"))
      (node (ref "R15") (pin "2") (pinfunction "2_2") (pintype "passive"))
    )
    (net (code "33") (name "Net-(OK1-C4)") (class "Default")
      (node (ref "OK1") (pin "10") (pinfunction "C4_10") (pintype "bidirectional"))
      (node (ref "R16") (pin "2") (pinfunction "2_2") (pintype "passive"))
    )
    (net (code "34") (name "Net-(OK2-C1)") (class "Default")
      (node (ref "OK2") (pin "16") (pinfunction "C1_16") (pintype "bidirectional"))
      (node (ref "R17") (pin "2") (pinfunction "2_2") (pintype "passive"))
    )
    (net (code "35") (name "Net-(OK2-C2)") (class "Default")
      (node (ref "OK2") (pin "14") (pinfunction "C2_14") (pintype "bidirectional"))
      (node (ref "R18") (pin "2") (pinfunction "2_2") (pintype "passive"))
    )
    (net (code "36") (name "Net-(OK2-C3)") (class "Default")
      (node (ref "OK2") (pin "12") (pinfunction "C3_12") (pintype "bidirectional"))
      (node (ref "R19") (pin "2") (pinfunction "2_2") (pintype "passive"))
    )
    (net (code "37") (name "Net-(OK2-C4)") (class "Default")
      (node (ref "OK2") (pin "10") (pinfunction "C4_10") (pintype "bidirectional"))
      (node (ref "R20") (pin "2") (pinfunction "2_2") (pintype "passive"))
    )
    (net (code "38") (name "Net-(OK3-A1)") (class "Default")
      (node (ref "OK3") (pin "1") (pinfunction "A1_1") (pintype "bidirectional"))
      (node (ref "R33") (pin "2") (pinfunction "2_2") (pintype "passive"))
    )
    (net (code "39") (name "Net-(U2-PLLFLTR)") (class "Default")
      (node (ref "R3") (pin "2") (pinfunction "2_2") (pintype "passive"))
      (node (ref "R4") (pin "1") (pinfunction "1_1") (pintype "passive"))
      (node (ref "U2") (pin "B8") (pinfunction "PLLFLTR_B8") (pintype "bidirectional"))
    )
    (net (code "40") (name "Net-(U2-V_FB)") (class "Default")
      (node (ref "R2") (pin "2") (pinfunction "2_2") (pintype "passive"))
      (node (ref "U2") (pin "B6") (pinfunction "V_FB_B6") (pintype "bidirectional"))
    )
    (net (code "41") (name "OK1E1") (class "Default")
      (node (ref "OK1") (pin "15") (pinfunction "E1_15") (pintype "bidirectional"))
      (node (ref "R25") (pin "2") (pinfunction "2_2") (pintype "passive"))
      (node (ref "U3") (pin "3") (pinfunction "INPUT1_3") (pintype "bidirectional"))
    )
    (net (code "42") (name "OK1E2") (class "Default")
      (node (ref "OK1") (pin "13") (pinfunction "E2_13") (pintype "bidirectional"))
      (node (ref "R26") (pin "2") (pinfunction "2_2") (pintype "passive"))
      (node (ref "U3") (pin "5") (pinfunction "INPUT2_5") (pintype "bidirectional"))
    )
    (net (code "43") (name "OK1E3") (class "Default")
      (node (ref "OK1") (pin "11") (pinfunction "E3_11") (pintype "bidirectional"))
      (node (ref "R27") (pin "2") (pinfunction "2_2") (pintype "passive"))
      (node (ref "U3") (pin "7") (pinfunction "INPUT3_7") (pintype "bidirectional"))
    )
    (net (code "44") (name "OK1E4") (class "Default")
      (node (ref "OK1") (pin "9") (pinfunction "E4_9") (pintype "bidirectional"))
      (node (ref "R28") (pin "2") (pinfunction "2_2") (pintype "passive"))
      (node (ref "U3") (pin "9") (pinfunction "INPUT4_9") (pintype "bidirectional"))
    )
    (net (code "45") (name "OK2E1") (class "Default")
      (node (ref "OK2") (pin "15") (pinfunction "E1_15") (pintype "bidirectional"))
      (node (ref "R21") (pin "2") (pinfunction "2_2") (pintype "passive"))
      (node (ref "U4") (pin "3") (pinfunction "INPUT1_3") (pintype "bidirectional"))
    )
    (net (code "46") (name "OK2E2") (class "Default")
      (node (ref "OK2") (pin "13") (pinfunction "E2_13") (pintype "bidirectional"))
      (node (ref "R22") (pin "2") (pinfunction "2_2") (pintype "passive"))
      (node (ref "U4") (pin "5") (pinfunction "INPUT2_5") (pintype "bidirectional"))
    )
    (net (code "47") (name "OK2E3") (class "Default")
      (node (ref "OK2") (pin "11") (pinfunction "E3_11") (pintype "bidirectional"))
      (node (ref "R23") (pin "2") (pinfunction "2_2") (pintype "passive"))
      (node (ref "U4") (pin "7") (pinfunction "INPUT3_7") (pintype "bidirectional"))
    )
    (net (code "48") (name "OK2E4") (class "Default")
      (node (ref "OK2") (pin "9") (pinfunction "E4_9") (pintype "bidirectional"))
      (node (ref "R24") (pin "2") (pinfunction "2_2") (pintype "passive"))
      (node (ref "U4") (pin "9") (pinfunction "INPUT4_9") (pintype "bidirectional"))
    )
    (net (code "49") (name "P18_SW1") (class "Default")
      (node (ref "OK1") (pin "1") (pinfunction "A1_1") (pintype "bidirectional"))
      (node (ref "R5") (pin "1") (pinfunction "1_1") (pintype "passive"))
    )
    (net (code "50") (name "P18_SW2") (class "Default")
      (node (ref "OK1") (pin "5") (pinfunction "A3_5") (pintype "bidirectional"))
      (node (ref "R6") (pin "1") (pinfunction "1_1") (pintype "passive"))
    )
    (net (code "51") (name "P18_SW3") (class "Default")
      (node (ref "OK2") (pin "1") (pinfunction "A1_1") (pintype "bidirectional"))
      (node (ref "R7") (pin "1") (pinfunction "1_1") (pintype "passive"))
    )
    (net (code "52") (name "P18_SW4") (class "Default")
      (node (ref "OK2") (pin "5") (pinfunction "A3_5") (pintype "bidirectional"))
      (node (ref "R8") (pin "1") (pinfunction "1_1") (pintype "passive"))
    )
    (net (code "53") (name "P18_SW5") (class "Default")
      (node (ref "OK1") (pin "3") (pinfunction "A2_3") (pintype "bidirectional"))
      (node (ref "R9") (pin "1") (pinfunction "1_1") (pintype "passive"))
    )
    (net (code "54") (name "P18_SW6") (class "Default")
      (node (ref "OK1") (pin "7") (pinfunction "A4_7") (pintype "bidirectional"))
      (node (ref "R10") (pin "1") (pinfunction "1_1") (pintype "passive"))
    )
    (net (code "55") (name "P18_SW7") (class "Default")
      (node (ref "OK2") (pin "3") (pinfunction "A2_3") (pintype "bidirectional"))
      (node (ref "R11") (pin "1") (pinfunction "1_1") (pintype "passive"))
    )
    (net (code "56") (name "P18_SW8") (class "Default")
      (node (ref "OK2") (pin "7") (pinfunction "A4_7") (pintype "bidirectional"))
      (node (ref "R12") (pin "1") (pinfunction "1_1") (pintype "passive"))
    )
    (net (code "57") (name "PGND") (class "Default")
      (node (ref "C3") (pin "2") (pinfunction "2_2") (pintype "passive"))
      (node (ref "C4") (pin "2") (pinfunction "2_2") (pintype "passive"))
      (node (ref "C5") (pin "K1") (pinfunction "K_K1") (pintype "passive"))
      (node (ref "J1") (pin "2") (pinfunction "-_2") (pintype "passive"))
      (node (ref "J3") (pin "2") (pinfunction "-_2") (pintype "passive"))
      (node (ref "J5") (pin "1") (pinfunction "1_1") (pintype "bidirectional"))
      (node (ref "J5") (pin "7") (pinfunction "7_7") (pintype "bidirectional"))
      (node (ref "J6") (pin "1") (pinfunction "1_1") (pintype "bidirectional"))
      (node (ref "J6") (pin "7") (pinfunction "7_7") (pintype "bidirectional"))
      (node (ref "R1") (pin "2") (pinfunction "2_2") (pintype "passive"))
      (node (ref "R21") (pin "1") (pinfunction "1_1") (pintype "passive"))
      (node (ref "R22") (pin "1") (pinfunction "1_1") (pintype "passive"))
      (node (ref "R23") (pin "1") (pinfunction "1_1") (pintype "passive"))
      (node (ref "R24") (pin "1") (pinfunction "1_1") (pintype "passive"))
      (node (ref "R25") (pin "1") (pinfunction "1_1") (pintype "passive"))
      (node (ref "R26") (pin "1") (pinfunction "1_1") (pintype "passive"))
      (node (ref "R27") (pin "1") (pinfunction "1_1") (pintype "passive"))
      (node (ref "R28") (pin "1") (pinfunction "1_1") (pintype "passive"))
      (node (ref "U2") (pin "A1") (pinfunction "PGND_A1") (pintype "bidirectional"))
      (node (ref "U2") (pin "A11") (pinfunction "PGND_A11") (pintype "bidirectional"))
      (node (ref "U2") (pin "A12") (pinfunction "PGND_A12") (pintype "bidirectional"))
      (node (ref "U2") (pin "A2") (pinfunction "PGND_A2") (pintype "bidirectional"))
      (node (ref "U2") (pin "A3") (pinfunction "PGND_A3") (pintype "bidirectional"))
      (node (ref "U2") (pin "A5") (pinfunction "SENSE-_A5") (pintype "bidirectional"))
      (node (ref "U2") (pin "B1") (pinfunction "PGND_B1") (pintype "bidirectional"))
      (node (ref "U2") (pin "B10") (pinfunction "PGND_B10") (pintype "bidirectional"))
      (node (ref "U2") (pin "B11") (pinfunction "PGND_B11") (pintype "bidirectional"))
      (node (ref "U2") (pin "B12") (pinfunction "PGND_B12") (pintype "bidirectional"))
      (node (ref "U2") (pin "B2") (pinfunction "PGND_B2") (pintype "bidirectional"))
      (node (ref "U2") (pin "B3") (pinfunction "PGND_B3") (pintype "bidirectional"))
      (node (ref "U2") (pin "B4") (pinfunction "PGND_B4") (pintype "bidirectional"))
      (node (ref "U2") (pin "C1") (pinfunction "PGND_C1") (pintype "bidirectional"))
      (node (ref "U2") (pin "C10") (pinfunction "PGND_C10") (pintype "bidirectional"))
      (node (ref "U2") (pin "C11") (pinfunction "PGND_C11") (pintype "bidirectional"))
      (node (ref "U2") (pin "C12") (pinfunction "PGND_C12") (pintype "bidirectional"))
      (node (ref "U2") (pin "C2") (pinfunction "PGND_C2") (pintype "bidirectional"))
      (node (ref "U2") (pin "C3") (pinfunction "PGND_C3") (pintype "bidirectional"))
      (node (ref "U2") (pin "C4") (pinfunction "PGND_C4") (pintype "bidirectional"))
      (node (ref "U2") (pin "C5") (pinfunction "PGND_C5") (pintype "bidirectional"))
      (node (ref "U2") (pin "C6") (pinfunction "PGND_C6") (pintype "bidirectional"))
      (node (ref "U2") (pin "C7") (pinfunction "PGND_C7") (pintype "bidirectional"))
      (node (ref "U2") (pin "C8") (pinfunction "PGND_C8") (pintype "bidirectional"))
      (node (ref "U2") (pin "C9") (pinfunction "PGND_C9") (pintype "bidirectional"))
      (node (ref "U2") (pin "D1") (pinfunction "PGND_D1") (pintype "bidirectional"))
      (node (ref "U2") (pin "D10") (pinfunction "PGND_D10") (pintype "bidirectional"))
      (node (ref "U2") (pin "D11") (pinfunction "PGND_D11") (pintype "bidirectional"))
      (node (ref "U2") (pin "D12") (pinfunction "PGND_D12") (pintype "bidirectional"))
      (node (ref "U2") (pin "D2") (pinfunction "PGND_D2") (pintype "bidirectional"))
      (node (ref "U2") (pin "D3") (pinfunction "PGND_D3") (pintype "bidirectional"))
      (node (ref "U2") (pin "D4") (pinfunction "PGND_D4") (pintype "bidirectional"))
      (node (ref "U2") (pin "D5") (pinfunction "PGND_D5") (pintype "bidirectional"))
      (node (ref "U2") (pin "D6") (pinfunction "PGND_D6") (pintype "bidirectional"))
      (node (ref "U2") (pin "D7") (pinfunction "PGND_D7") (pintype "bidirectional"))
      (node (ref "U2") (pin "D8") (pinfunction "PGND_D8") (pintype "bidirectional"))
      (node (ref "U2") (pin "D9") (pinfunction "PGND_D9") (pintype "bidirectional"))
      (node (ref "U2") (pin "E10") (pinfunction "PGND_E10") (pintype "bidirectional"))
      (node (ref "U2") (pin "E11") (pinfunction "PGND_E11") (pintype "bidirectional"))
      (node (ref "U2") (pin "E12") (pinfunction "PGND_E12") (pintype "bidirectional"))
      (node (ref "U2") (pin "E3") (pinfunction "PGND_E3") (pintype "bidirectional"))
      (node (ref "U2") (pin "E4") (pinfunction "PGND_E4") (pintype "bidirectional"))
      (node (ref "U2") (pin "E5") (pinfunction "PGND_E5") (pintype "bidirectional"))
      (node (ref "U2") (pin "E6") (pinfunction "PGND_E6") (pintype "bidirectional"))
      (node (ref "U2") (pin "E7") (pinfunction "PGND_E7") (pintype "bidirectional"))
      (node (ref "U2") (pin "E8") (pinfunction "PGND_E8") (pintype "bidirectional"))
      (node (ref "U2") (pin "E9") (pinfunction "PGND_E9") (pintype "bidirectional"))
      (node (ref "U3") (pin "1") (pinfunction "GND_1") (pintype "bidirectional"))
      (node (ref "U3") (pin "10") (pinfunction "GND_10") (pintype "bidirectional"))
      (node (ref "U4") (pin "1") (pinfunction "GND_1") (pintype "bidirectional"))
      (node (ref "U4") (pin "10") (pinfunction "GND_10") (pintype "bidirectional"))
    )
    (net (code "58") (name "PGOOD_PMA") (class "Default")
      (node (ref "U2") (pin "B5") (pinfunction "PGOOD_B5") (pintype "bidirectional"))
    )
    (net (code "59") (name "RSENSE") (class "Default")
      (node (ref "R1") (pin "1") (pinfunction "1_1") (pintype "passive"))
      (node (ref "U2") (pin "A4") (pinfunction "SENSE+_A4") (pintype "bidirectional"))
      (node (ref "U2") (pin "F10") (pinfunction "R_SENSE_F10") (pintype "bidirectional"))
      (node (ref "U2") (pin "F11") (pinfunction "R_SENSE_F11") (pintype "bidirectional"))
      (node (ref "U2") (pin "F12") (pinfunction "R_SENSE_F12") (pintype "bidirectional"))
      (node (ref "U2") (pin "G10") (pinfunction "R_SENSE_G10") (pintype "bidirectional"))
      (node (ref "U2") (pin "G11") (pinfunction "R_SENSE_G11") (pintype "bidirectional"))
      (node (ref "U2") (pin "G12") (pinfunction "R_SENSE_G12") (pintype "bidirectional"))
      (node (ref "U2") (pin "G5") (pinfunction "R_SENSE_G5") (pintype "bidirectional"))
      (node (ref "U2") (pin "G6") (pinfunction "R_SENSE_G6") (pintype "bidirectional"))
      (node (ref "U2") (pin "G7") (pinfunction "R_SENSE_G7") (pintype "bidirectional"))
      (node (ref "U2") (pin "G8") (pinfunction "R_SENSE_G8") (pintype "bidirectional"))
      (node (ref "U2") (pin "G9") (pinfunction "R_SENSE_G9") (pintype "bidirectional"))
      (node (ref "U2") (pin "H10") (pinfunction "R_SENSE_H10") (pintype "bidirectional"))
      (node (ref "U2") (pin "H11") (pinfunction "R_SENSE_H11") (pintype "bidirectional"))
      (node (ref "U2") (pin "H12") (pinfunction "R_SENSE_H12") (pintype "bidirectional"))
      (node (ref "U2") (pin "H5") (pinfunction "R_SENSE_H5") (pintype "bidirectional"))
      (node (ref "U2") (pin "H6") (pinfunction "R_SENSE_H6") (pintype "bidirectional"))
      (node (ref "U2") (pin "H7") (pinfunction "R_SENSE_H7") (pintype "bidirectional"))
      (node (ref "U2") (pin "H8") (pinfunction "R_SENSE_H8") (pintype "bidirectional"))
      (node (ref "U2") (pin "H9") (pinfunction "R_SENSE_H9") (pintype "bidirectional"))
      (node (ref "U2") (pin "J5") (pinfunction "R_SENSE_J5") (pintype "bidirectional"))
      (node (ref "U2") (pin "J6") (pinfunction "R_SENSE_J6") (pintype "bidirectional"))
      (node (ref "U2") (pin "J7") (pinfunction "R_SENSE_J7") (pintype "bidirectional"))
      (node (ref "U2") (pin "K5") (pinfunction "R_SENSE_K5") (pintype "bidirectional"))
      (node (ref "U2") (pin "K6") (pinfunction "R_SENSE_K6") (pintype "bidirectional"))
      (node (ref "U2") (pin "L5") (pinfunction "R_SENSE_L5") (pintype "bidirectional"))
      (node (ref "U2") (pin "L6") (pinfunction "R_SENSE_L6") (pintype "bidirectional"))
      (node (ref "U2") (pin "M5") (pinfunction "R_SENSE_M5") (pintype "bidirectional"))
      (node (ref "U2") (pin "M6") (pinfunction "R_SENSE_M6") (pintype "bidirectional"))
    )
    (net (code "60") (name "RUN_PMA") (class "Default")
      (node (ref "U2") (pin "A8") (pinfunction "RUN_A8") (pintype "bidirectional"))
    )
    (net (code "61") (name "SGND") (class "Default")
      (node (ref "J3") (pin "1") (pinfunction "+_1") (pintype "passive"))
      (node (ref "J5") (pin "3") (pinfunction "3_3") (pintype "bidirectional"))
      (node (ref "J5") (pin "9") (pinfunction "9_9") (pintype "bidirectional"))
      (node (ref "J6") (pin "3") (pinfunction "3_3") (pintype "bidirectional"))
      (node (ref "J6") (pin "9") (pinfunction "9_9") (pintype "bidirectional"))
      (node (ref "J7") (pin "2") (pinfunction "-_2") (pintype "passive"))
      (node (ref "OK1") (pin "2") (pinfunction "K1_2") (pintype "bidirectional"))
      (node (ref "OK1") (pin "4") (pinfunction "K2_4") (pintype "bidirectional"))
      (node (ref "OK1") (pin "6") (pinfunction "K3_6") (pintype "bidirectional"))
      (node (ref "OK1") (pin "8") (pinfunction "K4_8") (pintype "bidirectional"))
      (node (ref "OK2") (pin "2") (pinfunction "K1_2") (pintype "bidirectional"))
      (node (ref "OK2") (pin "4") (pinfunction "K2_4") (pintype "bidirectional"))
      (node (ref "OK2") (pin "6") (pinfunction "K3_6") (pintype "bidirectional"))
      (node (ref "OK2") (pin "8") (pinfunction "K4_8") (pintype "bidirectional"))
      (node (ref "OK3") (pin "15") (pinfunction "E1_15") (pintype "bidirectional"))
      (node (ref "R2") (pin "1") (pinfunction "1_1") (pintype "passive"))
      (node (ref "R4") (pin "2") (pinfunction "2_2") (pintype "passive"))
      (node (ref "U2") (pin "A7") (pinfunction "SGND_A7") (pintype "bidirectional"))
    )
    (net (code "62") (name "SW3V") (class "Default")
      (node (ref "R33") (pin "1") (pinfunction "1_1") (pintype "passive"))
      (node (ref "TP1") (pin "1") (pinfunction "1_1") (pintype "bidirectional"))
      (node (ref "U1") (pin "17") (pinfunction "VCC3V_17") (pintype "bidirectional"))
      (node (ref "U1") (pin "47") (pinfunction "VCC3V_47") (pintype "bidirectional"))
    )
    (net (code "63") (name "SW3V_GND") (class "Default")
      (node (ref "J7") (pin "1") (pinfunction "+_1") (pintype "passive"))
      (node (ref "TP2") (pin "1") (pinfunction "1_1") (pintype "bidirectional"))
      (node (ref "U1") (pin "48") (pinfunction "GND_48") (pintype "bidirectional"))
    )
    (net (code "64") (name "SW_P18H1") (class "Default")
      (node (ref "R9") (pin "2") (pinfunction "2_2") (pintype "passive"))
      (node (ref "U1") (pin "35") (pinfunction "SDHC_DAT0_35") (pintype "bidirectional"))
    )
    (net (code "65") (name "SW_P18H2") (class "Default")
      (node (ref "R10") (pin "2") (pinfunction "2_2") (pintype "passive"))
      (node (ref "U1") (pin "34") (pinfunction "UART1_TX_34") (pintype "bidirectional"))
    )
    (net (code "66") (name "SW_P18H3") (class "Default")
      (node (ref "R11") (pin "2") (pinfunction "2_2") (pintype "passive"))
      (node (ref "U1") (pin "33") (pinfunction "SDHC_CMD_33") (pintype "bidirectional"))
    )
    (net (code "67") (name "SW_P18H4") (class "Default")
      (node (ref "R12") (pin "2") (pinfunction "2_2") (pintype "passive"))
      (node (ref "U1") (pin "32") (pinfunction "UART1_RX_32") (pintype "bidirectional"))
    )
    (net (code "68") (name "SW_P18L1") (class "Default")
      (node (ref "R5") (pin "2") (pinfunction "2_2") (pintype "passive"))
      (node (ref "U1") (pin "39") (pinfunction "SDHC_DAT2_39") (pintype "bidirectional"))
    )
    (net (code "69") (name "SW_P18L2") (class "Default")
      (node (ref "R6") (pin "2") (pinfunction "2_2") (pintype "passive"))
      (node (ref "U1") (pin "38") (pinfunction "UART1_CTS_38") (pintype "bidirectional"))
    )
    (net (code "70") (name "SW_P18L3") (class "Default")
      (node (ref "R7") (pin "2") (pinfunction "2_2") (pintype "passive"))
      (node (ref "U1") (pin "37") (pinfunction "SDHC_DAT1_37") (pintype "bidirectional"))
    )
    (net (code "71") (name "SW_P18L4") (class "Default")
      (node (ref "R8") (pin "2") (pinfunction "2_2") (pintype "passive"))
      (node (ref "U1") (pin "36") (pinfunction "UART1_RTS_36") (pintype "bidirectional"))
    )
    (net (code "72") (name "TP_CH1") (class "Default")
      (node (ref "OK3") (pin "2") (pinfunction "K1_2") (pintype "bidirectional"))
      (node (ref "TP4") (pin "1") (pinfunction "1_1") (pintype "bidirectional"))
      (node (ref "U1") (pin "31") (pinfunction "SDHC_CLK_31") (pintype "bidirectional"))
    )
    (net (code "73") (name "V+") (class "Default")
      (node (ref "J4") (pin "2") (pinfunction "-_2") (pintype "passive"))
      (node (ref "U3") (pin "11") (pinfunction "V+_11") (pintype "bidirectional"))
      (node (ref "U3") (pin "13") (pinfunction "SENSE4_13") (pintype "bidirectional"))
      (node (ref "U3") (pin "15") (pinfunction "SENSE3_15") (pintype "bidirectional"))
      (node (ref "U3") (pin "17") (pinfunction "SENSE2_17") (pintype "bidirectional"))
      (node (ref "U3") (pin "19") (pinfunction "SENSE1_19") (pintype "bidirectional"))
      (node (ref "U3") (pin "20") (pinfunction "V+_20") (pintype "bidirectional"))
      (node (ref "U4") (pin "11") (pinfunction "V+_11") (pintype "bidirectional"))
      (node (ref "U4") (pin "13") (pinfunction "SENSE4_13") (pintype "bidirectional"))
      (node (ref "U4") (pin "15") (pinfunction "SENSE3_15") (pintype "bidirectional"))
      (node (ref "U4") (pin "17") (pinfunction "SENSE2_17") (pintype "bidirectional"))
      (node (ref "U4") (pin "19") (pinfunction "SENSE1_19") (pintype "bidirectional"))
      (node (ref "U4") (pin "20") (pinfunction "V+_20") (pintype "bidirectional"))
    )
    (net (code "74") (name "VBATT") (class "Default")
      (node (ref "C1") (pin "A1") (pinfunction "A_A1") (pintype "passive"))
      (node (ref "J2") (pin "97") (pinfunction "VBATT_97") (pintype "bidirectional"))
      (node (ref "J2") (pin "98") (pinfunction "VBATT_98") (pintype "bidirectional"))
      (node (ref "L2") (pin "1") (pinfunction "1_1") (pintype "bidirectional"))
    )
    (net (code "75") (name "VBATT_GND") (class "Default")
      (node (ref "C1") (pin "K1") (pinfunction "K_K1") (pintype "passive"))
      (node (ref "C2") (pin "2") (pinfunction "2_2") (pintype "passive"))
      (node (ref "J1") (pin "1") (pinfunction "+_1") (pintype "passive"))
      (node (ref "J2") (pin "81") (pinfunction "GND_81") (pintype "bidirectional"))
      (node (ref "J2") (pin "82") (pinfunction "GND_82") (pintype "bidirectional"))
      (node (ref "J2") (pin "83") (pinfunction "GND_83") (pintype "bidirectional"))
      (node (ref "J2") (pin "84") (pinfunction "GND_84") (pintype "bidirectional"))
    )
    (net (code "76") (name "VIN") (class "Default")
      (node (ref "C2") (pin "1") (pinfunction "1_1") (pintype "passive"))
      (node (ref "L2") (pin "2") (pinfunction "2_2") (pintype "bidirectional"))
      (node (ref "U2") (pin "J10") (pinfunction "V_IN_J10") (pintype "bidirectional"))
      (node (ref "U2") (pin "J11") (pinfunction "V_IN_J11") (pintype "bidirectional"))
      (node (ref "U2") (pin "J12") (pinfunction "V_IN_J12") (pintype "bidirectional"))
      (node (ref "U2") (pin "K10") (pinfunction "V_IN_K10") (pintype "bidirectional"))
      (node (ref "U2") (pin "K11") (pinfunction "V_IN_K11") (pintype "bidirectional"))
      (node (ref "U2") (pin "K12") (pinfunction "V_IN_K12") (pintype "bidirectional"))
      (node (ref "U2") (pin "L10") (pinfunction "V_IN_L10") (pintype "bidirectional"))
      (node (ref "U2") (pin "L11") (pinfunction "V_IN_L11") (pintype "bidirectional"))
      (node (ref "U2") (pin "L12") (pinfunction "V_IN_L12") (pintype "bidirectional"))
      (node (ref "U2") (pin "M10") (pinfunction "V_IN_M10") (pintype "bidirectional"))
      (node (ref "U2") (pin "M11") (pinfunction "V_IN_M11") (pintype "bidirectional"))
      (node (ref "U2") (pin "M12") (pinfunction "V_IN_M12") (pintype "bidirectional"))
    )
    (net (code "77") (name "VOUT") (class "Default")
      (node (ref "C3") (pin "1") (pinfunction "1_1") (pintype "passive"))
      (node (ref "C4") (pin "1") (pinfunction "1_1") (pintype "passive"))
      (node (ref "L3") (pin "1") (pinfunction "1_1") (pintype "bidirectional"))
      (node (ref "U2") (pin "E1") (pinfunction "V_OUT_E1") (pintype "bidirectional"))
      (node (ref "U2") (pin "E2") (pinfunction "V_OUT_E2") (pintype "bidirectional"))
      (node (ref "U2") (pin "F1") (pinfunction "V_OUT_F1") (pintype "bidirectional"))
      (node (ref "U2") (pin "F2") (pinfunction "V_OUT_F2") (pintype "bidirectional"))
      (node (ref "U2") (pin "F3") (pinfunction "V_OUT_F3") (pintype "bidirectional"))
      (node (ref "U2") (pin "F4") (pinfunction "V_OUT_F4") (pintype "bidirectional"))
      (node (ref "U2") (pin "G1") (pinfunction "V_OUT_G1") (pintype "bidirectional"))
      (node (ref "U2") (pin "G2") (pinfunction "V_OUT_G2") (pintype "bidirectional"))
      (node (ref "U2") (pin "G3") (pinfunction "V_OUT_G3") (pintype "bidirectional"))
      (node (ref "U2") (pin "G4") (pinfunction "V_OUT_G4") (pintype "bidirectional"))
      (node (ref "U2") (pin "H2") (pinfunction "V_OUT_H2") (pintype "bidirectional"))
      (node (ref "U2") (pin "H3") (pinfunction "V_OUT_H3") (pintype "bidirectional"))
      (node (ref "U2") (pin "H4") (pinfunction "V_OUT_H4") (pintype "bidirectional"))
      (node (ref "U2") (pin "VOUT") (pinfunction "V_OUT_VOUT") (pintype "bidirectional"))
    )
    (net (code "78") (name "VOUTA") (class "Default")
      (node (ref "C5") (pin "A1") (pinfunction "A_A1") (pintype "passive"))
      (node (ref "J4") (pin "1") (pinfunction "+_1") (pintype "passive"))
      (node (ref "L3") (pin "2") (pinfunction "2_2") (pintype "bidirectional"))
      (node (ref "Q1") (pin "D") (pinfunction "D_D") (pintype "bidirectional"))
      (node (ref "Q2") (pin "D") (pinfunction "D_D") (pintype "bidirectional"))
      (node (ref "Q4") (pin "D") (pinfunction "D_D") (pintype "bidirectional"))
      (node (ref "Q6") (pin "D") (pinfunction "D_D") (pintype "bidirectional"))
      (node (ref "R13") (pin "1") (pinfunction "1_1") (pintype "passive"))
      (node (ref "R14") (pin "1") (pinfunction "1_1") (pintype "passive"))
      (node (ref "R15") (pin "1") (pinfunction "1_1") (pintype "passive"))
      (node (ref "R16") (pin "1") (pinfunction "1_1") (pintype "passive"))
      (node (ref "R17") (pin "1") (pinfunction "1_1") (pintype "passive"))
      (node (ref "R18") (pin "1") (pinfunction "1_1") (pintype "passive"))
      (node (ref "R19") (pin "1") (pinfunction "1_1") (pintype "passive"))
      (node (ref "R20") (pin "1") (pinfunction "1_1") (pintype "passive"))
      (node (ref "R29") (pin "2") (pinfunction "2_2") (pintype "passive"))
      (node (ref "R30") (pin "2") (pinfunction "2_2") (pintype "passive"))
      (node (ref "R31") (pin "2") (pinfunction "2_2") (pintype "passive"))
      (node (ref "R32") (pin "2") (pinfunction "2_2") (pintype "passive"))
    )
    (net (code "79") (name "unconnected-(J2-+5V_SW-Pad33)") (class "Default")
      (node (ref "J2") (pin "33") (pinfunction "+5V_SW_33") (pintype "bidirectional"))
    )
    (net (code "80") (name "unconnected-(J2-+5V_SYS-Pad77)") (class "Default")
      (node (ref "J2") (pin "77") (pinfunction "+5V_SYS_77") (pintype "bidirectional"))
    )
    (net (code "81") (name "unconnected-(J2-+5V_SYS-Pad78)") (class "Default")
      (node (ref "J2") (pin "78") (pinfunction "+5V_SYS_78") (pintype "bidirectional"))
    )
    (net (code "82") (name "unconnected-(J2-+5V_USB-Pad32)") (class "Default")
      (node (ref "J2") (pin "32") (pinfunction "+5V_USB_32") (pintype "bidirectional"))
    )
    (net (code "83") (name "unconnected-(J2--CTS_MHX-Pad35)") (class "Default")
      (node (ref "J2") (pin "35") (pinfunction "-CTS_MHX_35") (pintype "bidirectional"))
    )
    (net (code "84") (name "unconnected-(J2--DSR_MHX-Pad37)") (class "Default")
      (node (ref "J2") (pin "37") (pinfunction "-DSR_MHX_37") (pintype "bidirectional"))
    )
    (net (code "85") (name "unconnected-(J2--DTR_MHX-Pad38)") (class "Default")
      (node (ref "J2") (pin "38") (pinfunction "-DTR_MHX_38") (pintype "bidirectional"))
    )
    (net (code "86") (name "unconnected-(J2--FAULT-Pad25)") (class "Default")
      (node (ref "J2") (pin "25") (pinfunction "-FAULT_25") (pintype "bidirectional"))
    )
    (net (code "87") (name "unconnected-(J2--RESET-Pad29)") (class "Default")
      (node (ref "J2") (pin "29") (pinfunction "-RESET_29") (pintype "bidirectional"))
    )
    (net (code "88") (name "unconnected-(J2--RST_MHX-Pad34)") (class "Default")
      (node (ref "J2") (pin "34") (pinfunction "-RST_MHX_34") (pintype "bidirectional"))
    )
    (net (code "89") (name "unconnected-(J2--RTS_MHX-Pad36)") (class "Default")
      (node (ref "J2") (pin "36") (pinfunction "-RTS_MHX_36") (pintype "bidirectional"))
    )
    (net (code "90") (name "unconnected-(J2-OFF_VCC-Pad31)") (class "Default")
      (node (ref "J2") (pin "31") (pinfunction "OFF_VCC_31") (pintype "bidirectional"))
    )
    (net (code "91") (name "unconnected-(J2-P1.0-Pad68)") (class "Default")
      (node (ref "J2") (pin "68") (pinfunction "P1.0_68") (pintype "bidirectional"))
    )
    (net (code "92") (name "unconnected-(J2-P1.1-Pad67)") (class "Default")
      (node (ref "J2") (pin "67") (pinfunction "P1.1_67") (pintype "bidirectional"))
    )
    (net (code "93") (name "unconnected-(J2-P1.2-Pad66)") (class "Default")
      (node (ref "J2") (pin "66") (pinfunction "P1.2_66") (pintype "bidirectional"))
    )
    (net (code "94") (name "unconnected-(J2-P1.3-Pad65)") (class "Default")
      (node (ref "J2") (pin "65") (pinfunction "P1.3_65") (pintype "bidirectional"))
    )
    (net (code "95") (name "unconnected-(J2-P1.4-Pad64)") (class "Default")
      (node (ref "J2") (pin "64") (pinfunction "P1.4_64") (pintype "bidirectional"))
    )
    (net (code "96") (name "unconnected-(J2-P1.5-Pad63)") (class "Default")
      (node (ref "J2") (pin "63") (pinfunction "P1.5_63") (pintype "bidirectional"))
    )
    (net (code "97") (name "unconnected-(J2-P1.6-Pad62)") (class "Default")
      (node (ref "J2") (pin "62") (pinfunction "P1.6_62") (pintype "bidirectional"))
    )
    (net (code "98") (name "unconnected-(J2-P1.7-Pad61)") (class "Default")
      (node (ref "J2") (pin "61") (pinfunction "P1.7_61") (pintype "bidirectional"))
    )
    (net (code "99") (name "unconnected-(J2-P2.0-Pad76)") (class "Default")
      (node (ref "J2") (pin "76") (pinfunction "P2.0_76") (pintype "bidirectional"))
    )
    (net (code "100") (name "unconnected-(J2-P2.1-Pad75)") (class "Default")
      (node (ref "J2") (pin "75") (pinfunction "P2.1_75") (pintype "bidirectional"))
    )
    (net (code "101") (name "unconnected-(J2-P2.2-Pad74)") (class "Default")
      (node (ref "J2") (pin "74") (pinfunction "P2.2_74") (pintype "bidirectional"))
    )
    (net (code "102") (name "unconnected-(J2-P2.3-Pad73)") (class "Default")
      (node (ref "J2") (pin "73") (pinfunction "P2.3_73") (pintype "bidirectional"))
    )
    (net (code "103") (name "unconnected-(J2-P2.4-Pad72)") (class "Default")
      (node (ref "J2") (pin "72") (pinfunction "P2.4_72") (pintype "bidirectional"))
    )
    (net (code "104") (name "unconnected-(J2-P2.5-Pad71)") (class "Default")
      (node (ref "J2") (pin "71") (pinfunction "P2.5_71") (pintype "bidirectional"))
    )
    (net (code "105") (name "unconnected-(J2-P2.6-Pad70)") (class "Default")
      (node (ref "J2") (pin "70") (pinfunction "P2.6_70") (pintype "bidirectional"))
    )
    (net (code "106") (name "unconnected-(J2-P2.7-Pad69)") (class "Default")
      (node (ref "J2") (pin "69") (pinfunction "P2.7_69") (pintype "bidirectional"))
    )
    (net (code "107") (name "unconnected-(J2-P3.0-Pad24)") (class "Default")
      (node (ref "J2") (pin "24") (pinfunction "P3.0_24") (pintype "bidirectional"))
    )
    (net (code "108") (name "unconnected-(J2-P3.1-Pad23)") (class "Default")
      (node (ref "J2") (pin "23") (pinfunction "P3.1_23") (pintype "bidirectional"))
    )
    (net (code "109") (name "unconnected-(J2-P3.2-Pad22)") (class "Default")
      (node (ref "J2") (pin "22") (pinfunction "P3.2_22") (pintype "bidirectional"))
    )
    (net (code "110") (name "unconnected-(J2-P3.3-Pad21)") (class "Default")
      (node (ref "J2") (pin "21") (pinfunction "P3.3_21") (pintype "bidirectional"))
    )
    (net (code "111") (name "unconnected-(J2-P3.4-Pad20)") (class "Default")
      (node (ref "J2") (pin "20") (pinfunction "P3.4_20") (pintype "bidirectional"))
    )
    (net (code "112") (name "unconnected-(J2-P3.5-Pad19)") (class "Default")
      (node (ref "J2") (pin "19") (pinfunction "P3.5_19") (pintype "bidirectional"))
    )
    (net (code "113") (name "unconnected-(J2-P3.6-Pad18)") (class "Default")
      (node (ref "J2") (pin "18") (pinfunction "P3.6_18") (pintype "bidirectional"))
    )
    (net (code "114") (name "unconnected-(J2-P3.7-Pad17)") (class "Default")
      (node (ref "J2") (pin "17") (pinfunction "P3.7_17") (pintype "bidirectional"))
    )
    (net (code "115") (name "unconnected-(J2-P4.0-Pad16)") (class "Default")
      (node (ref "J2") (pin "16") (pinfunction "P4.0_16") (pintype "bidirectional"))
    )
    (net (code "116") (name "unconnected-(J2-P4.1-Pad15)") (class "Default")
      (node (ref "J2") (pin "15") (pinfunction "P4.1_15") (pintype "bidirectional"))
    )
    (net (code "117") (name "unconnected-(J2-P4.2-Pad14)") (class "Default")
      (node (ref "J2") (pin "14") (pinfunction "P4.2_14") (pintype "bidirectional"))
    )
    (net (code "118") (name "unconnected-(J2-P4.3-Pad13)") (class "Default")
      (node (ref "J2") (pin "13") (pinfunction "P4.3_13") (pintype "bidirectional"))
    )
    (net (code "119") (name "unconnected-(J2-P4.4-Pad12)") (class "Default")
      (node (ref "J2") (pin "12") (pinfunction "P4.4_12") (pintype "bidirectional"))
    )
    (net (code "120") (name "unconnected-(J2-P4.5-Pad11)") (class "Default")
      (node (ref "J2") (pin "11") (pinfunction "P4.5_11") (pintype "bidirectional"))
    )
    (net (code "121") (name "unconnected-(J2-P4.6-Pad10)") (class "Default")
      (node (ref "J2") (pin "10") (pinfunction "P4.6_10") (pintype "bidirectional"))
    )
    (net (code "122") (name "unconnected-(J2-P4.7-Pad9)") (class "Default")
      (node (ref "J2") (pin "9") (pinfunction "P4.7_9") (pintype "bidirectional"))
    )
    (net (code "123") (name "unconnected-(J2-P5.0-Pad8)") (class "Default")
      (node (ref "J2") (pin "8") (pinfunction "P5.0_8") (pintype "bidirectional"))
    )
    (net (code "124") (name "unconnected-(J2-P5.1-Pad7)") (class "Default")
      (node (ref "J2") (pin "7") (pinfunction "P5.1_7") (pintype "bidirectional"))
    )
    (net (code "125") (name "unconnected-(J2-P5.2-Pad6)") (class "Default")
      (node (ref "J2") (pin "6") (pinfunction "P5.2_6") (pintype "bidirectional"))
    )
    (net (code "126") (name "unconnected-(J2-P5.3-Pad5)") (class "Default")
      (node (ref "J2") (pin "5") (pinfunction "P5.3_5") (pintype "bidirectional"))
    )
    (net (code "127") (name "unconnected-(J2-P5.4-Pad4)") (class "Default")
      (node (ref "J2") (pin "4") (pinfunction "P5.4_4") (pintype "bidirectional"))
    )
    (net (code "128") (name "unconnected-(J2-P5.5-Pad3)") (class "Default")
      (node (ref "J2") (pin "3") (pinfunction "P5.5_3") (pintype "bidirectional"))
    )
    (net (code "129") (name "unconnected-(J2-P5.6-Pad2)") (class "Default")
      (node (ref "J2") (pin "2") (pinfunction "P5.6_2") (pintype "bidirectional"))
    )
    (net (code "130") (name "unconnected-(J2-P5.7-Pad1)") (class "Default")
      (node (ref "J2") (pin "1") (pinfunction "P5.7_1") (pintype "bidirectional"))
    )
    (net (code "131") (name "unconnected-(J2-P6.0-Pad60)") (class "Default")
      (node (ref "J2") (pin "60") (pinfunction "P6.0_60") (pintype "bidirectional"))
    )
    (net (code "132") (name "unconnected-(J2-P6.1-Pad59)") (class "Default")
      (node (ref "J2") (pin "59") (pinfunction "P6.1_59") (pintype "bidirectional"))
    )
    (net (code "133") (name "unconnected-(J2-P6.2-Pad58)") (class "Default")
      (node (ref "J2") (pin "58") (pinfunction "P6.2_58") (pintype "bidirectional"))
    )
    (net (code "134") (name "unconnected-(J2-P6.3-Pad57)") (class "Default")
      (node (ref "J2") (pin "57") (pinfunction "P6.3_57") (pintype "bidirectional"))
    )
    (net (code "135") (name "unconnected-(J2-P6.4-Pad56)") (class "Default")
      (node (ref "J2") (pin "56") (pinfunction "P6.4_56") (pintype "bidirectional"))
    )
    (net (code "136") (name "unconnected-(J2-P6.5-Pad55)") (class "Default")
      (node (ref "J2") (pin "55") (pinfunction "P6.5_55") (pintype "bidirectional"))
    )
    (net (code "137") (name "unconnected-(J2-P6.6-Pad54)") (class "Default")
      (node (ref "J2") (pin "54") (pinfunction "P6.6_54") (pintype "bidirectional"))
    )
    (net (code "138") (name "unconnected-(J2-P6.7-Pad53)") (class "Default")
      (node (ref "J2") (pin "53") (pinfunction "P6.7_53") (pintype "bidirectional"))
    )
    (net (code "139") (name "unconnected-(J2-RSVD0-Pad44)") (class "Default")
      (node (ref "J2") (pin "44") (pinfunction "RSVD0_44") (pintype "bidirectional"))
    )
    (net (code "140") (name "unconnected-(J2-RSVD1-Pad45)") (class "Default")
      (node (ref "J2") (pin "45") (pinfunction "RSVD1_45") (pintype "bidirectional"))
    )
    (net (code "141") (name "unconnected-(J2-RSVD2-Pad46)") (class "Default")
      (node (ref "J2") (pin "46") (pinfunction "RSVD2_46") (pintype "bidirectional"))
    )
    (net (code "142") (name "unconnected-(J2-RXD_MHX-Pad40)") (class "Default")
      (node (ref "J2") (pin "40") (pinfunction "RXD_MHX_40") (pintype "bidirectional"))
    )
    (net (code "143") (name "unconnected-(J2-SENSE-Pad27)") (class "Default")
      (node (ref "J2") (pin "27") (pinfunction "SENSE_27") (pintype "bidirectional"))
    )
    (net (code "144") (name "unconnected-(J2-SW0-Pad85)") (class "Default")
      (node (ref "J2") (pin "85") (pinfunction "SW0_85") (pintype "bidirectional"))
    )
    (net (code "145") (name "unconnected-(J2-SW0-Pad86)") (class "Default")
      (node (ref "J2") (pin "86") (pinfunction "SW0_86") (pintype "bidirectional"))
    )
    (net (code "146") (name "unconnected-(J2-SW1-Pad87)") (class "Default")
      (node (ref "J2") (pin "87") (pinfunction "SW1_87") (pintype "bidirectional"))
    )
    (net (code "147") (name "unconnected-(J2-SW1-Pad88)") (class "Default")
      (node (ref "J2") (pin "88") (pinfunction "SW1_88") (pintype "bidirectional"))
    )
    (net (code "148") (name "unconnected-(J2-SW2-Pad89)") (class "Default")
      (node (ref "J2") (pin "89") (pinfunction "SW2_89") (pintype "bidirectional"))
    )
    (net (code "149") (name "unconnected-(J2-SW2-Pad90)") (class "Default")
      (node (ref "J2") (pin "90") (pinfunction "SW2_90") (pintype "bidirectional"))
    )
    (net (code "150") (name "unconnected-(J2-SW3-Pad91)") (class "Default")
      (node (ref "J2") (pin "91") (pinfunction "SW3_91") (pintype "bidirectional"))
    )
    (net (code "151") (name "unconnected-(J2-SW3-Pad92)") (class "Default")
      (node (ref "J2") (pin "92") (pinfunction "SW3_92") (pintype "bidirectional"))
    )
    (net (code "152") (name "unconnected-(J2-SW4-Pad93)") (class "Default")
      (node (ref "J2") (pin "93") (pinfunction "SW4_93") (pintype "bidirectional"))
    )
    (net (code "153") (name "unconnected-(J2-SW4-Pad94)") (class "Default")
      (node (ref "J2") (pin "94") (pinfunction "SW4_94") (pintype "bidirectional"))
    )
    (net (code "154") (name "unconnected-(J2-SW5-Pad95)") (class "Default")
      (node (ref "J2") (pin "95") (pinfunction "SW5_95") (pintype "bidirectional"))
    )
    (net (code "155") (name "unconnected-(J2-SW5-Pad96)") (class "Default")
      (node (ref "J2") (pin "96") (pinfunction "SW5_96") (pintype "bidirectional"))
    )
    (net (code "156") (name "unconnected-(J2-TXD_MHX-Pad39)") (class "Default")
      (node (ref "J2") (pin "39") (pinfunction "TXD_MHX_39") (pintype "bidirectional"))
    )
    (net (code "157") (name "unconnected-(J2-USER0-Pad47)") (class "Default")
      (node (ref "J2") (pin "47") (pinfunction "USER0_47") (pintype "bidirectional"))
    )
    (net (code "158") (name "unconnected-(J2-USER1-Pad48)") (class "Default")
      (node (ref "J2") (pin "48") (pinfunction "USER1_48") (pintype "bidirectional"))
    )
    (net (code "159") (name "unconnected-(J2-USER2-Pad49)") (class "Default")
      (node (ref "J2") (pin "49") (pinfunction "USER2_49") (pintype "bidirectional"))
    )
    (net (code "160") (name "unconnected-(J2-USER3-Pad50)") (class "Default")
      (node (ref "J2") (pin "50") (pinfunction "USER3_50") (pintype "bidirectional"))
    )
    (net (code "161") (name "unconnected-(J2-USER4-Pad51)") (class "Default")
      (node (ref "J2") (pin "51") (pinfunction "USER4_51") (pintype "bidirectional"))
    )
    (net (code "162") (name "unconnected-(J2-USER5-Pad52)") (class "Default")
      (node (ref "J2") (pin "52") (pinfunction "USER5_52") (pintype "bidirectional"))
    )
    (net (code "163") (name "unconnected-(J2-USER6-Pad99)") (class "Default")
      (node (ref "J2") (pin "99") (pinfunction "USER6_99") (pintype "bidirectional"))
    )
    (net (code "164") (name "unconnected-(J2-USER7-Pad100)") (class "Default")
      (node (ref "J2") (pin "100") (pinfunction "USER7_100") (pintype "bidirectional"))
    )
    (net (code "165") (name "unconnected-(J2-USER8-Pad101)") (class "Default")
      (node (ref "J2") (pin "101") (pinfunction "USER8_101") (pintype "bidirectional"))
    )
    (net (code "166") (name "unconnected-(J2-USER9-Pad102)") (class "Default")
      (node (ref "J2") (pin "102") (pinfunction "USER9_102") (pintype "bidirectional"))
    )
    (net (code "167") (name "unconnected-(J2-USER10-Pad103)") (class "Default")
      (node (ref "J2") (pin "103") (pinfunction "USER10_103") (pintype "bidirectional"))
    )
    (net (code "168") (name "unconnected-(J2-USER11-Pad104)") (class "Default")
      (node (ref "J2") (pin "104") (pinfunction "USER11_104") (pintype "bidirectional"))
    )
    (net (code "169") (name "unconnected-(J2-VBACKUP-Pad42)") (class "Default")
      (node (ref "J2") (pin "42") (pinfunction "VBACKUP_42") (pintype "bidirectional"))
    )
    (net (code "170") (name "unconnected-(J2-VCC_SYS-Pad79)") (class "Default")
      (node (ref "J2") (pin "79") (pinfunction "VCC_SYS_79") (pintype "bidirectional"))
    )
    (net (code "171") (name "unconnected-(J2-VCC_SYS-Pad80)") (class "Default")
      (node (ref "J2") (pin "80") (pinfunction "VCC_SYS_80") (pintype "bidirectional"))
    )
    (net (code "172") (name "unconnected-(J2-VEREF+-Pad28)") (class "Default")
      (node (ref "J2") (pin "28") (pinfunction "VEREF+_28") (pintype "bidirectional"))
    )
    (net (code "173") (name "unconnected-(J2-VREF+-Pad26)") (class "Default")
      (node (ref "J2") (pin "26") (pinfunction "VREF+_26") (pintype "bidirectional"))
    )
    (net (code "174") (name "unconnected-(J2-VREF--Pad30)") (class "Default")
      (node (ref "J2") (pin "30") (pinfunction "VREF-_30") (pintype "bidirectional"))
    )
    (net (code "175") (name "unconnected-(J5-Pad6)") (class "Default")
      (node (ref "J5") (pin "6") (pinfunction "6_6") (pintype "bidirectional"))
    )
    (net (code "176") (name "unconnected-(J5-Pad12)") (class "Default")
      (node (ref "J5") (pin "12") (pinfunction "12_12") (pintype "bidirectional"))
    )
    (net (code "177") (name "unconnected-(J6-Pad6)") (class "Default")
      (node (ref "J6") (pin "6") (pinfunction "6_6") (pintype "bidirectional"))
    )
    (net (code "178") (name "unconnected-(J6-Pad12)") (class "Default")
      (node (ref "J6") (pin "12") (pinfunction "12_12") (pintype "bidirectional"))
    )
    (net (code "179") (name "unconnected-(OK3-A2-Pad3)") (class "Default")
      (node (ref "OK3") (pin "3") (pinfunction "A2_3") (pintype "bidirectional"))
    )
    (net (code "180") (name "unconnected-(OK3-A3-Pad5)") (class "Default")
      (node (ref "OK3") (pin "5") (pinfunction "A3_5") (pintype "bidirectional"))
    )
    (net (code "181") (name "unconnected-(OK3-A4-Pad7)") (class "Default")
      (node (ref "OK3") (pin "7") (pinfunction "A4_7") (pintype "bidirectional"))
    )
    (net (code "182") (name "unconnected-(OK3-C2-Pad14)") (class "Default")
      (node (ref "OK3") (pin "14") (pinfunction "C2_14") (pintype "bidirectional"))
    )
    (net (code "183") (name "unconnected-(OK3-C3-Pad12)") (class "Default")
      (node (ref "OK3") (pin "12") (pinfunction "C3_12") (pintype "bidirectional"))
    )
    (net (code "184") (name "unconnected-(OK3-C4-Pad10)") (class "Default")
      (node (ref "OK3") (pin "10") (pinfunction "C4_10") (pintype "bidirectional"))
    )
    (net (code "185") (name "unconnected-(OK3-E2-Pad13)") (class "Default")
      (node (ref "OK3") (pin "13") (pinfunction "E2_13") (pintype "bidirectional"))
    )
    (net (code "186") (name "unconnected-(OK3-E3-Pad11)") (class "Default")
      (node (ref "OK3") (pin "11") (pinfunction "E3_11") (pintype "bidirectional"))
    )
    (net (code "187") (name "unconnected-(OK3-E4-Pad9)") (class "Default")
      (node (ref "OK3") (pin "9") (pinfunction "E4_9") (pintype "bidirectional"))
    )
    (net (code "188") (name "unconnected-(OK3-K2-Pad4)") (class "Default")
      (node (ref "OK3") (pin "4") (pinfunction "K2_4") (pintype "bidirectional"))
    )
    (net (code "189") (name "unconnected-(OK3-K3-Pad6)") (class "Default")
      (node (ref "OK3") (pin "6") (pinfunction "K3_6") (pintype "bidirectional"))
    )
    (net (code "190") (name "unconnected-(OK3-K4-Pad8)") (class "Default")
      (node (ref "OK3") (pin "8") (pinfunction "K4_8") (pintype "bidirectional"))
    )
    (net (code "191") (name "unconnected-(U1-ADC_IN0-Pad2)") (class "Default")
      (node (ref "U1") (pin "2") (pinfunction "ADC_IN0_2") (pintype "bidirectional"))
    )
    (net (code "192") (name "unconnected-(U1-ADC_IN1-Pad1)") (class "Default")
      (node (ref "U1") (pin "1") (pinfunction "ADC_IN1_1") (pintype "bidirectional"))
    )
    (net (code "193") (name "unconnected-(U1-ADC_IN2-Pad4)") (class "Default")
      (node (ref "U1") (pin "4") (pinfunction "ADC_IN2_4") (pintype "bidirectional"))
    )
    (net (code "194") (name "unconnected-(U1-ADC_IN3-Pad3)") (class "Default")
      (node (ref "U1") (pin "3") (pinfunction "ADC_IN3_3") (pintype "bidirectional"))
    )
    (net (code "195") (name "unconnected-(U1-ADC_IN4-Pad6)") (class "Default")
      (node (ref "U1") (pin "6") (pinfunction "ADC_IN4_6") (pintype "bidirectional"))
    )
    (net (code "196") (name "unconnected-(U1-ADC_IN7-Pad5)") (class "Default")
      (node (ref "U1") (pin "5") (pinfunction "ADC_IN7_5") (pintype "bidirectional"))
    )
    (net (code "197") (name "unconnected-(U1-AGND-Pad8)") (class "Default")
      (node (ref "U1") (pin "8") (pinfunction "AGND_8") (pintype "bidirectional"))
    )
    (net (code "198") (name "unconnected-(U1-CAN1_RX-Pad20)") (class "Default")
      (node (ref "U1") (pin "20") (pinfunction "CAN1_RX_20") (pintype "bidirectional"))
    )
    (net (code "199") (name "unconnected-(U1-CAN1_TX-Pad22)") (class "Default")
      (node (ref "U1") (pin "22") (pinfunction "CAN1_TX_22") (pintype "bidirectional"))
    )
    (net (code "200") (name "unconnected-(U1-ERX_JM-Pad44)") (class "Default")
      (node (ref "U1") (pin "44") (pinfunction "ERX_JM_44") (pintype "bidirectional"))
    )
    (net (code "201") (name "unconnected-(U1-ERX_JP-Pad43)") (class "Default")
      (node (ref "U1") (pin "43") (pinfunction "ERX_JP_43") (pintype "bidirectional"))
    )
    (net (code "202") (name "unconnected-(U1-ETX_JM-Pad46)") (class "Default")
      (node (ref "U1") (pin "46") (pinfunction "ETX_JM_46") (pintype "bidirectional"))
    )
    (net (code "203") (name "unconnected-(U1-ETX_JP-Pad45)") (class "Default")
      (node (ref "U1") (pin "45") (pinfunction "ETX_JP_45") (pintype "bidirectional"))
    )
    (net (code "204") (name "unconnected-(U1-GND-Pad18)") (class "Default")
      (node (ref "U1") (pin "18") (pinfunction "GND_18") (pintype "bidirectional"))
    )
    (net (code "205") (name "unconnected-(U1-IRQ2-Pad50)") (class "Default")
      (node (ref "U1") (pin "50") (pinfunction "IRQ2_50") (pintype "bidirectional"))
    )
    (net (code "206") (name "unconnected-(U1-IRQ3-Pad49)") (class "Default")
      (node (ref "U1") (pin "49") (pinfunction "IRQ3_49") (pintype "bidirectional"))
    )
    (net (code "207") (name "unconnected-(U1-IRQ7-Pad9)") (class "Default")
      (node (ref "U1") (pin "9") (pinfunction "IRQ7_9") (pintype "bidirectional"))
    )
    (net (code "208") (name "unconnected-(U1-LINKLED-Pad42)") (class "Default")
      (node (ref "U1") (pin "42") (pinfunction "LINKLED_42") (pintype "bidirectional"))
    )
    (net (code "209") (name "unconnected-(U1-OW_DAT-Pad12)") (class "Default")
      (node (ref "U1") (pin "12") (pinfunction "OW_DAT_12") (pintype "bidirectional"))
    )
    (net (code "210") (name "unconnected-(U1-RSTI-Pad11)") (class "Default")
      (node (ref "U1") (pin "11") (pinfunction "RSTI_11") (pintype "bidirectional"))
    )
    (net (code "211") (name "unconnected-(U1-SDHC_DAT3-Pad15)") (class "Default")
      (node (ref "U1") (pin "15") (pinfunction "SDHC_DAT3_15") (pintype "bidirectional"))
    )
    (net (code "212") (name "unconnected-(U1-SPEEDLED-Pad40)") (class "Default")
      (node (ref "U1") (pin "40") (pinfunction "SPEEDLED_40") (pintype "bidirectional"))
    )
    (net (code "213") (name "unconnected-(U1-T0IN-Pad19)") (class "Default")
      (node (ref "U1") (pin "19") (pinfunction "T0IN_19") (pintype "bidirectional"))
    )
    (net (code "214") (name "unconnected-(U1-T1IN-Pad21)") (class "Default")
      (node (ref "U1") (pin "21") (pinfunction "T1IN_21") (pintype "bidirectional"))
    )
    (net (code "215") (name "unconnected-(U1-T2IN-Pad23)") (class "Default")
      (node (ref "U1") (pin "23") (pinfunction "T2IN_23") (pintype "bidirectional"))
    )
    (net (code "216") (name "unconnected-(U1-T3IN-Pad25)") (class "Default")
      (node (ref "U1") (pin "25") (pinfunction "T3IN_25") (pintype "bidirectional"))
    )
    (net (code "217") (name "unconnected-(U1-UART0_CTS-Pad30)") (class "Default")
      (node (ref "U1") (pin "30") (pinfunction "UART0_CTS_30") (pintype "bidirectional"))
    )
    (net (code "218") (name "unconnected-(U1-UART0_RTS-Pad28)") (class "Default")
      (node (ref "U1") (pin "28") (pinfunction "UART0_RTS_28") (pintype "bidirectional"))
    )
    (net (code "219") (name "unconnected-(U1-UART0_RX-Pad24)") (class "Default")
      (node (ref "U1") (pin "24") (pinfunction "UART0_RX_24") (pintype "bidirectional"))
    )
    (net (code "220") (name "unconnected-(U1-UART0_TX-Pad26)") (class "Default")
      (node (ref "U1") (pin "26") (pinfunction "UART0_TX_26") (pintype "bidirectional"))
    )
    (net (code "221") (name "unconnected-(U1-UART2_CTS-Pad10)") (class "Default")
      (node (ref "U1") (pin "10") (pinfunction "UART2_CTS_10") (pintype "bidirectional"))
    )
    (net (code "222") (name "unconnected-(U1-UART2_RTS-Pad14)") (class "Default")
      (node (ref "U1") (pin "14") (pinfunction "UART2_RTS_14") (pintype "bidirectional"))
    )
    (net (code "223") (name "unconnected-(U1-UART2_RX-Pad13)") (class "Default")
      (node (ref "U1") (pin "13") (pinfunction "UART2_RX_13") (pintype "bidirectional"))
    )
    (net (code "224") (name "unconnected-(U1-UART2_TX-Pad16)") (class "Default")
      (node (ref "U1") (pin "16") (pinfunction "UART2_TX_16") (pintype "bidirectional"))
    )
    (net (code "225") (name "unconnected-(U1-USBO_DM-Pad51)") (class "Default")
      (node (ref "U1") (pin "51") (pinfunction "USBO_DM_51") (pintype "bidirectional"))
    )
    (net (code "226") (name "unconnected-(U1-USBO_DP-Pad52)") (class "Default")
      (node (ref "U1") (pin "52") (pinfunction "USBO_DP_52") (pintype "bidirectional"))
    )
    (net (code "227") (name "unconnected-(U1-VCC3VE-Pad41)") (class "Default")
      (node (ref "U1") (pin "41") (pinfunction "VCC3VE_41") (pintype "bidirectional"))
    )
    (net (code "228") (name "unconnected-(U1-VDDA_DAC_ADC-Pad7)") (class "Default")
      (node (ref "U1") (pin "7") (pinfunction "VDDA_DAC_ADC_7") (pintype "bidirectional"))
    )
    (net (code "229") (name "unconnected-(U2-COMP-PadB7)") (class "Default")
      (node (ref "U2") (pin "B7") (pinfunction "COMP_B7") (pintype "bidirectional"))
    )
    (net (code "230") (name "unconnected-(U2-EXTV_CC-PadF6)") (class "Default")
      (node (ref "U2") (pin "F6") (pinfunction "EXTV_CC_F6") (pintype "bidirectional"))
    )
    (net (code "231") (name "unconnected-(U2-PLLIN-PadB9)") (class "Default")
      (node (ref "U2") (pin "B9") (pinfunction "PLLIN_B9") (pintype "bidirectional"))
    )
    (net (code "232") (name "unconnected-(U2-SS-PadA6)") (class "Default")
      (node (ref "U2") (pin "A6") (pinfunction "SS_A6") (pintype "bidirectional"))
    )
    (net (code "233") (name "unconnected-(U2-STBYMD-PadA10)") (class "Default")
      (node (ref "U2") (pin "A10") (pinfunction "STBYMD_A10") (pintype "bidirectional"))
    )
    (net (code "234") (name "unconnected-(U3-TIMER1-Pad2)") (class "Default")
      (node (ref "U3") (pin "2") (pinfunction "TIMER1_2") (pintype "bidirectional"))
    )
    (net (code "235") (name "unconnected-(U3-TIMER2-Pad4)") (class "Default")
      (node (ref "U3") (pin "4") (pinfunction "TIMER2_4") (pintype "bidirectional"))
    )
    (net (code "236") (name "unconnected-(U3-TIMER3-Pad6)") (class "Default")
      (node (ref "U3") (pin "6") (pinfunction "TIMER3_6") (pintype "bidirectional"))
    )
    (net (code "237") (name "unconnected-(U3-TIMER4-Pad8)") (class "Default")
      (node (ref "U3") (pin "8") (pinfunction "TIMER4_8") (pintype "bidirectional"))
    )
    (net (code "238") (name "unconnected-(U4-TIMER1-Pad2)") (class "Default")
      (node (ref "U4") (pin "2") (pinfunction "TIMER1_2") (pintype "bidirectional"))
    )
    (net (code "239") (name "unconnected-(U4-TIMER2-Pad4)") (class "Default")
      (node (ref "U4") (pin "4") (pinfunction "TIMER2_4") (pintype "bidirectional"))
    )
    (net (code "240") (name "unconnected-(U4-TIMER3-Pad6)") (class "Default")
      (node (ref "U4") (pin "6") (pinfunction "TIMER3_6") (pintype "bidirectional"))
    )
    (net (code "241") (name "unconnected-(U4-TIMER4-Pad8)") (class "Default")
      (node (ref "U4") (pin "8") (pinfunction "TIMER4_8") (pintype "bidirectional"))
    )
  )
)
